# 03_-_28PINS_SCHEMATIC.net
KiCad netlist of a schematic drawn in Altium Designer
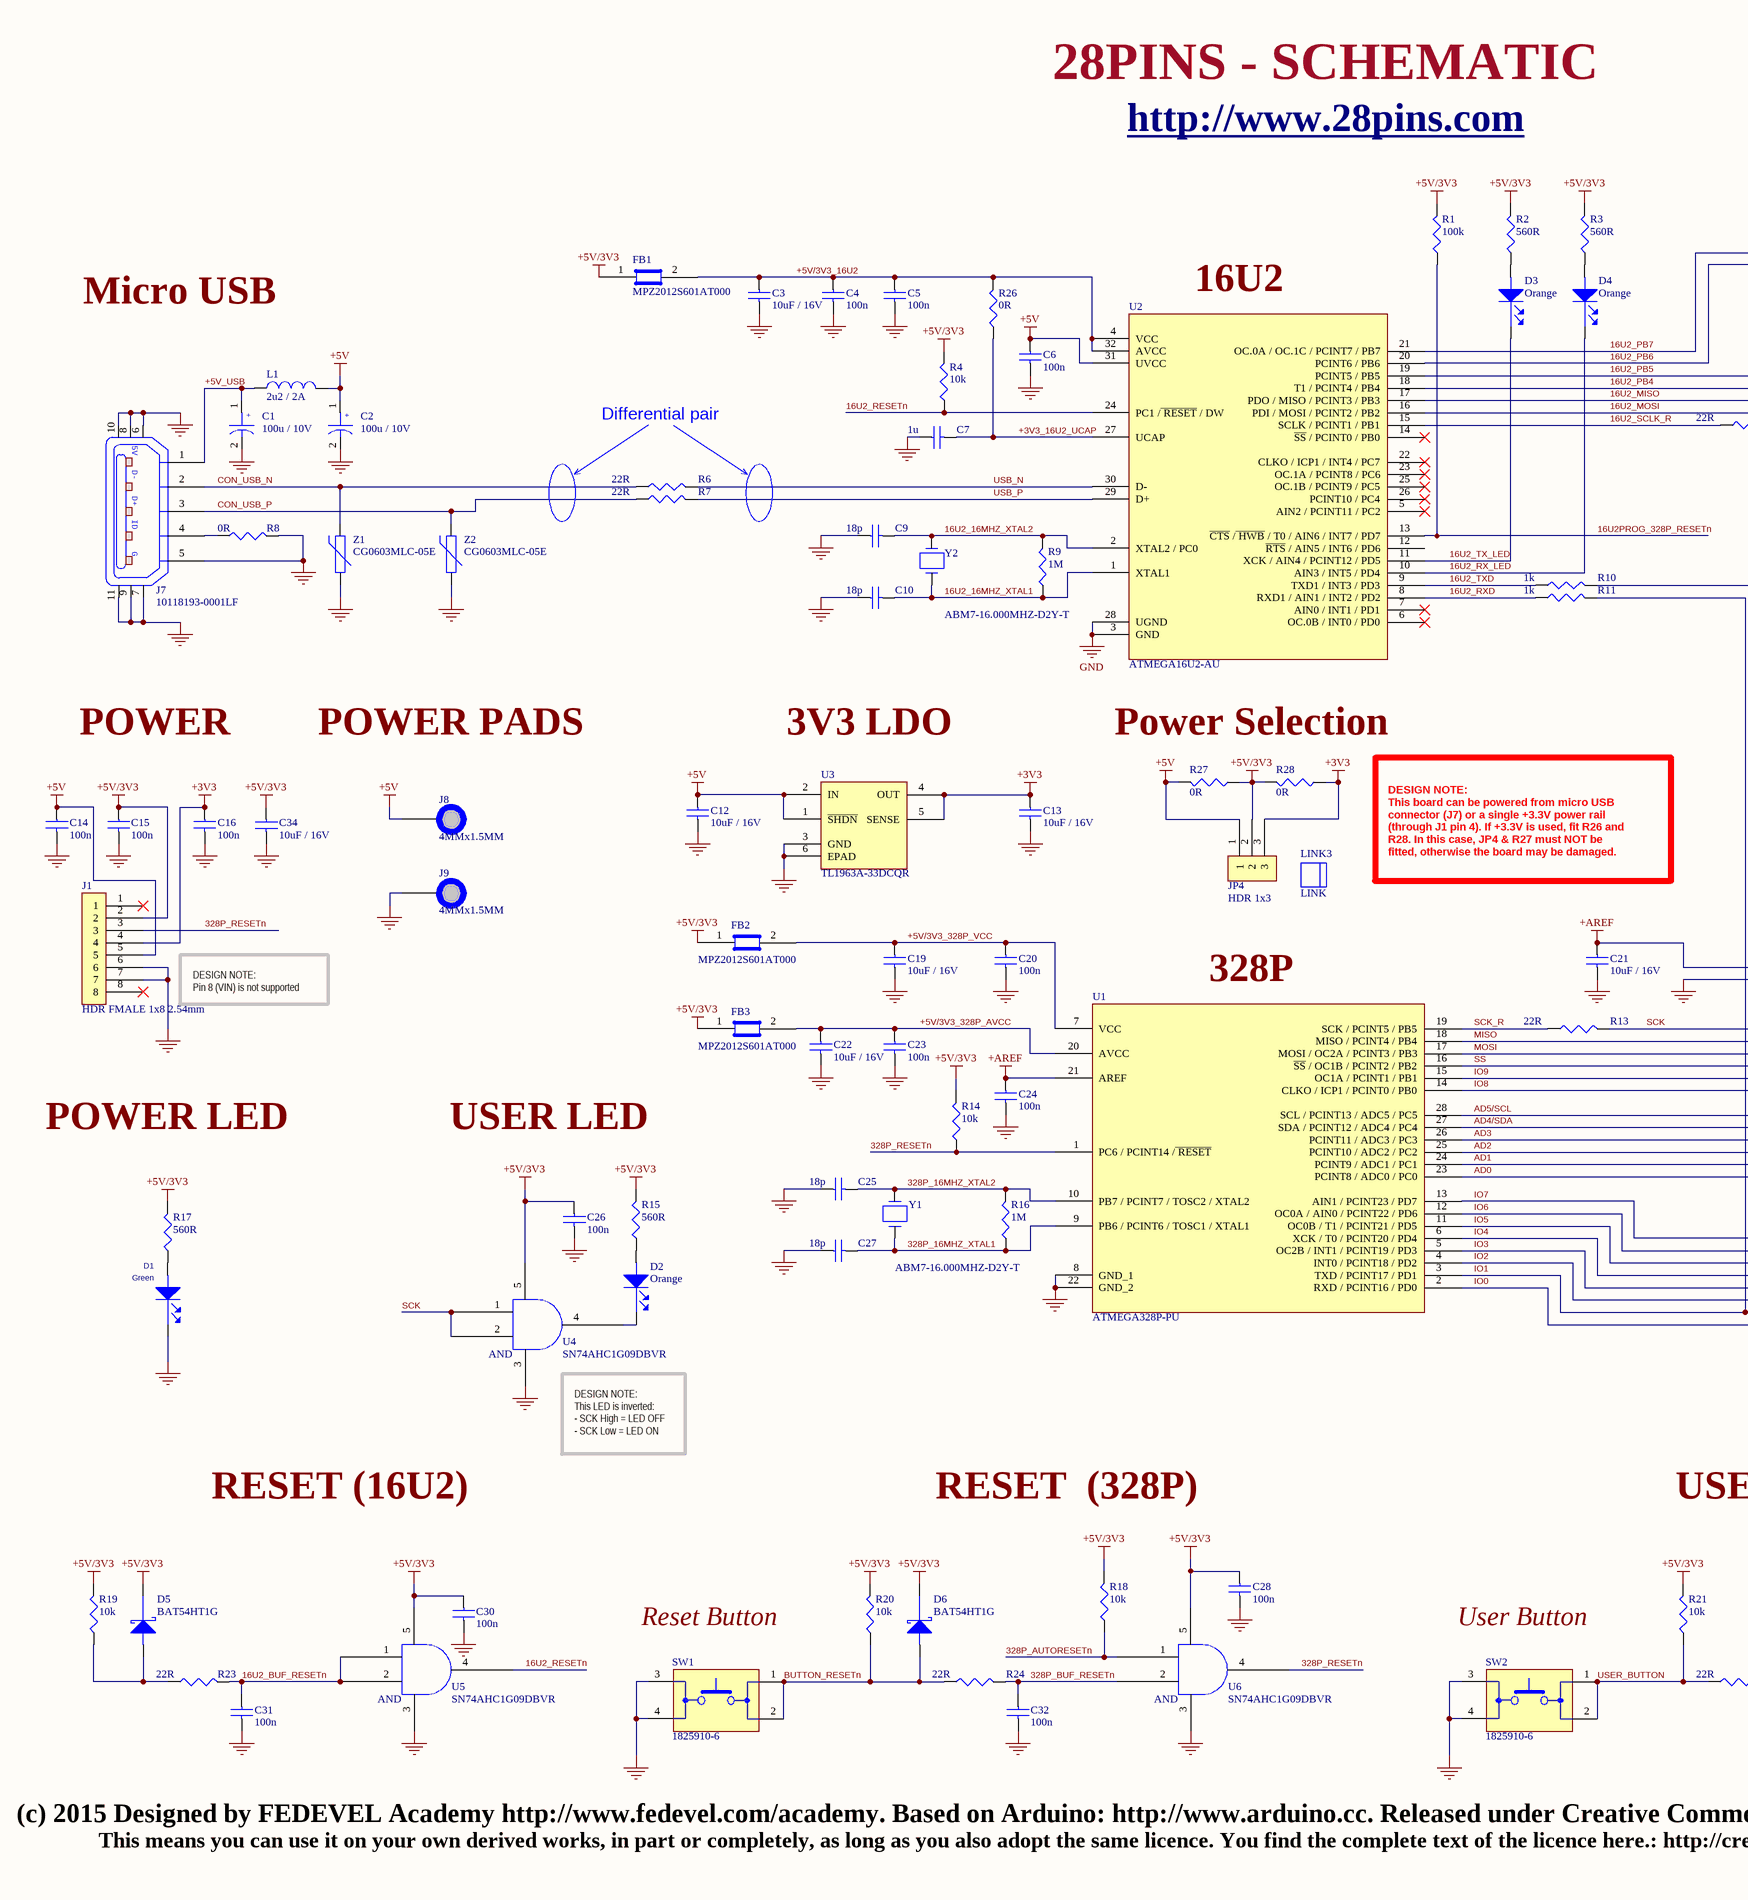
[diagram p0: [03] - 28PINS SCHEMATIC.SchDoc, left]
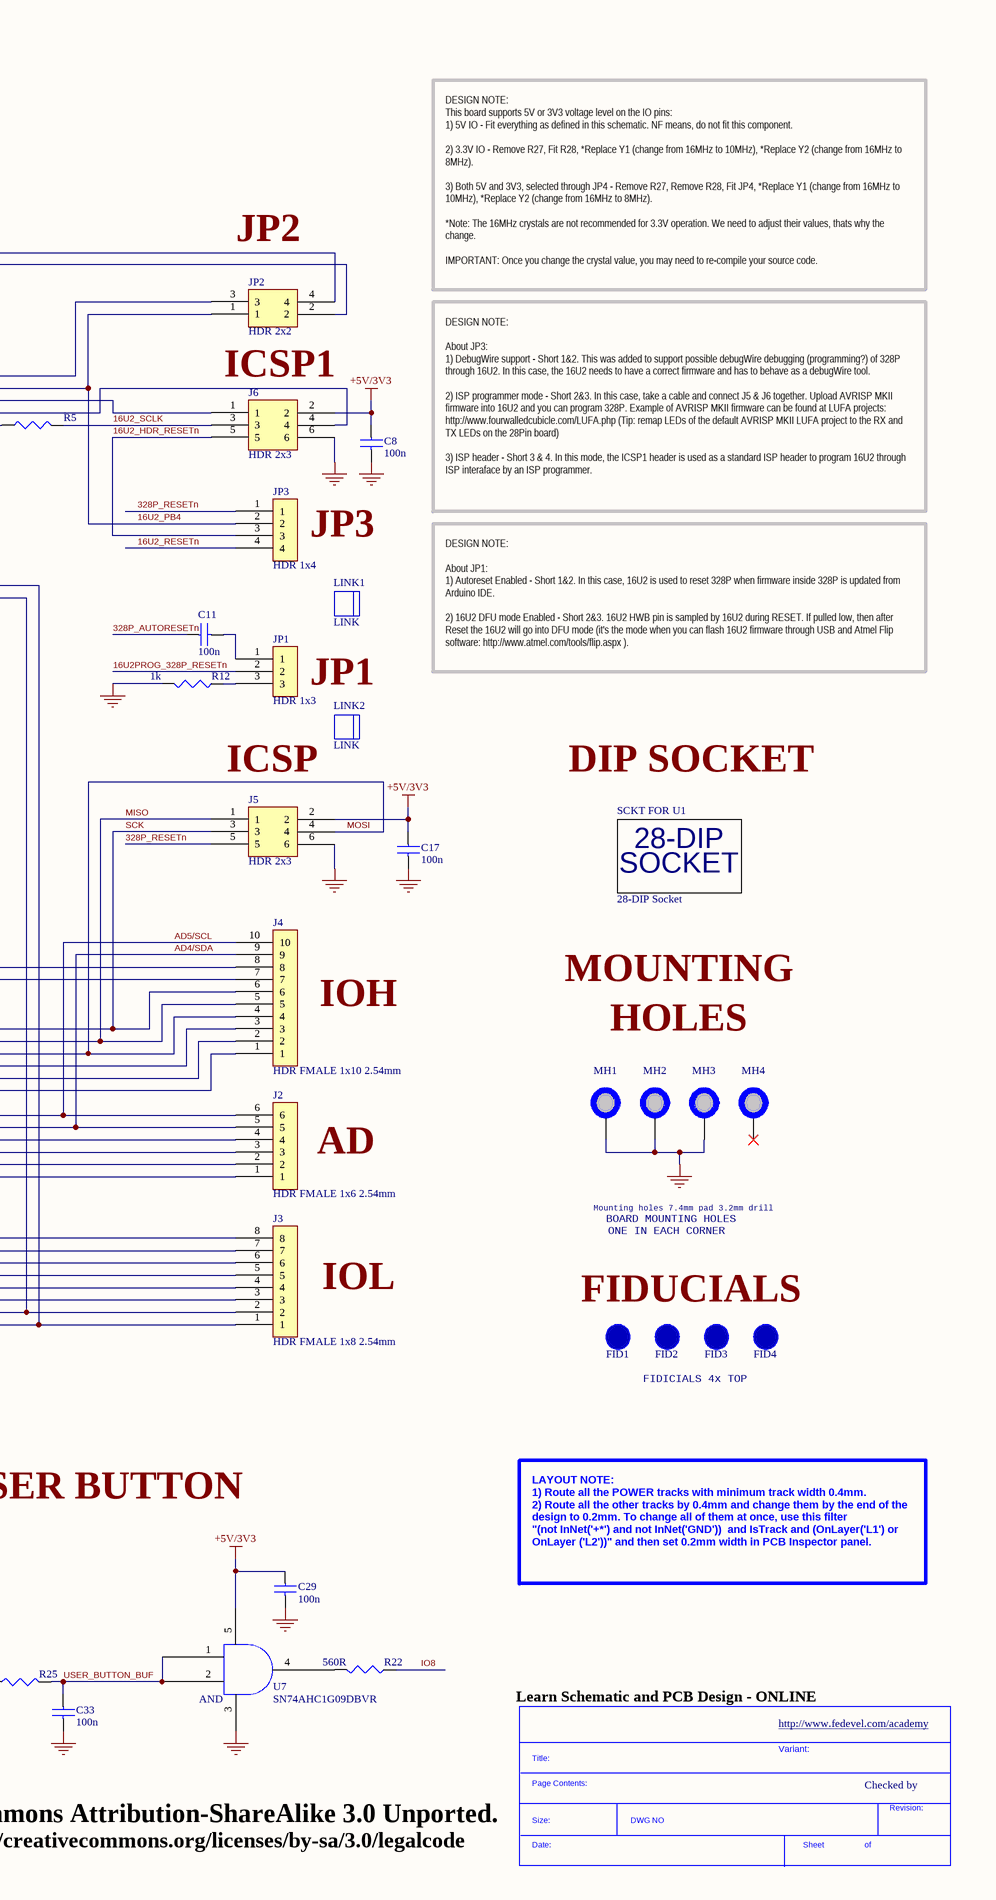
[diagram p1: [03] - 28PINS SCHEMATIC.SchDoc, right]

(export (version "E")
  (design (tool "Eeschema 10.0.6"))
  (components
    (comp (ref "C1")
      (value "100u / 10V")
      (footprint "C_ALU_C_SIZE")
      (description "CAP ALUM 100UF 10V 20% SMD")
      (fields
        (field (name "MANUFACTURER") "Panasonic Electronic Components")
        (field (name "MANUFACTURER PART NUMBER") "EEE-1AA101WR")
        (field (name ".CREATOR") "MM")
        (field (name ".CHECKED PCB") "RF")
        (field (name ".CHECKED SCH") "RF")
      )
      (libsource (lib "Integrated_Library_FEDEVEL_APR_2015") (part "EEE-1AA101WR"))
    )
    (comp (ref "C2")
      (value "100u / 10V")
      (footprint "C_ALU_C_SIZE")
      (description "CAP ALUM 100UF 10V 20% SMD")
      (fields
        (field (name "MANUFACTURER") "Panasonic Electronic Components")
        (field (name "MANUFACTURER PART NUMBER") "EEE-1AA101WR")
        (field (name ".CREATOR") "MM")
        (field (name ".CHECKED PCB") "RF")
        (field (name ".CHECKED SCH") "RF")
      )
      (libsource (lib "Integrated_Library_FEDEVEL_APR_2015") (part "EEE-1AA101WR"))
    )
    (comp (ref "C3")
      (value "10uF / 16V")
      (footprint "C0805")
      (description "CAP CER 10UF 16V 20% X5R 0805")
      (fields
        (field (name "MANUFACTURER") "TDK Corporation")
        (field (name "MANUFACTURER PART NUMBER") "C2012X5R1C106M/1.25")
      )
      (libsource (lib "Integrated_Library_FEDEVEL_APR_2015") (part "C2012X5R1C106M"))
    )
    (comp (ref "C4")
      (value "100n")
      (footprint "C0805")
      (description "CAP CER 0.1UF 50V 10% X7R 0805")
      (fields
        (field (name "MANUFACTURER") "TDK Corporation")
        (field (name "MANUFACTURER PART NUMBER") "C2012X7R1H104K085AA")
        (field (name ".CREATOR") "MM")
        (field (name ".CHECKED PCB") "RF")
        (field (name ".CHECKED SCH") "RF")
      )
      (libsource (lib "Integrated_Library_FEDEVEL_APR_2015") (part "C2012X7R1H104K085AA"))
    )
    (comp (ref "C5")
      (value "100n")
      (footprint "C0805")
      (description "CAP CER 0.1UF 50V 10% X7R 0805")
      (fields
        (field (name "MANUFACTURER") "TDK Corporation")
        (field (name "MANUFACTURER PART NUMBER") "C2012X7R1H104K085AA")
        (field (name ".CREATOR") "MM")
        (field (name ".CHECKED PCB") "RF")
        (field (name ".CHECKED SCH") "RF")
      )
      (libsource (lib "Integrated_Library_FEDEVEL_APR_2015") (part "C2012X7R1H104K085AA"))
    )
    (comp (ref "C6")
      (value "100n")
      (footprint "C0805")
      (description "CAP CER 0.1UF 50V 10% X7R 0805")
      (fields
        (field (name "MANUFACTURER") "TDK Corporation")
        (field (name "MANUFACTURER PART NUMBER") "C2012X7R1H104K085AA")
        (field (name ".CREATOR") "MM")
        (field (name ".CHECKED PCB") "RF")
        (field (name ".CHECKED SCH") "RF")
      )
      (libsource (lib "Integrated_Library_FEDEVEL_APR_2015") (part "C2012X7R1H104K085AA"))
    )
    (comp (ref "C7")
      (value "1u")
      (footprint "C0805")
      (description "CAP CER 1UF 25V 10% X5R 0805")
      (fields
        (field (name "MANUFACTURER") "TDK Corporation")
        (field (name "MANUFACTURER PART NUMBER") "C2012X5R1E105K125AA")
        (field (name ".CREATOR") "MM")
        (field (name ".CHECKED PCB") "RF")
        (field (name ".CHECKED SCH") "RF")
      )
      (libsource (lib "Integrated_Library_FEDEVEL_APR_2015") (part "C2012X5R1E105K125AA"))
    )
    (comp (ref "C8")
      (value "100n")
      (footprint "C0805")
      (description "CAP CER 0.1UF 50V 10% X7R 0805")
      (fields
        (field (name "MANUFACTURER") "TDK Corporation")
        (field (name "MANUFACTURER PART NUMBER") "C2012X7R1H104K085AA")
        (field (name ".CREATOR") "MM")
        (field (name ".CHECKED PCB") "RF")
        (field (name ".CHECKED SCH") "RF")
      )
      (libsource (lib "Integrated_Library_FEDEVEL_APR_2015") (part "C2012X7R1H104K085AA"))
    )
    (comp (ref "C9")
      (value "18p")
      (footprint "C0805")
      (description "CAP CER 18PF 50V 5% NP0 0805")
      (fields
        (field (name "MANUFACTURER") "Kemet")
        (field (name "MANUFACTURER PART NUMBER") "C0805C180J5GACTU")
        (field (name ".CREATOR") "MM")
        (field (name ".CHECKED PCB") "RF")
        (field (name ".CHECKED SCH") "RF")
      )
      (libsource (lib "Integrated_Library_FEDEVEL_APR_2015") (part "C0805C180J5GACTU"))
    )
    (comp (ref "C10")
      (value "18p")
      (footprint "C0805")
      (description "CAP CER 18PF 50V 5% NP0 0805")
      (fields
        (field (name "MANUFACTURER") "Kemet")
        (field (name "MANUFACTURER PART NUMBER") "C0805C180J5GACTU")
        (field (name ".CREATOR") "MM")
        (field (name ".CHECKED PCB") "RF")
        (field (name ".CHECKED SCH") "RF")
      )
      (libsource (lib "Integrated_Library_FEDEVEL_APR_2015") (part "C0805C180J5GACTU"))
    )
    (comp (ref "C11")
      (value "100n")
      (footprint "C0805")
      (description "CAP CER 0.1UF 50V 10% X7R 0805")
      (fields
        (field (name "MANUFACTURER") "TDK Corporation")
        (field (name "MANUFACTURER PART NUMBER") "C2012X7R1H104K085AA")
        (field (name ".CREATOR") "MM")
        (field (name ".CHECKED PCB") "RF")
        (field (name ".CHECKED SCH") "RF")
      )
      (libsource (lib "Integrated_Library_FEDEVEL_APR_2015") (part "C2012X7R1H104K085AA"))
    )
    (comp (ref "C12")
      (value "10uF / 16V")
      (footprint "C0805")
      (description "CAP CER 10UF 16V 20% X5R 0805")
      (fields
        (field (name "MANUFACTURER") "TDK Corporation")
        (field (name "MANUFACTURER PART NUMBER") "C2012X5R1C106M/1.25")
      )
      (libsource (lib "Integrated_Library_FEDEVEL_APR_2015") (part "C2012X5R1C106M"))
    )
    (comp (ref "C13")
      (value "10uF / 16V")
      (footprint "C0805")
      (description "CAP CER 10UF 16V 20% X5R 0805")
      (fields
        (field (name "MANUFACTURER") "TDK Corporation")
        (field (name "MANUFACTURER PART NUMBER") "C2012X5R1C106M/1.25")
      )
      (libsource (lib "Integrated_Library_FEDEVEL_APR_2015") (part "C2012X5R1C106M"))
    )
    (comp (ref "C14")
      (value "100n")
      (footprint "C0805")
      (description "CAP CER 0.1UF 50V 10% X7R 0805")
      (fields
        (field (name "MANUFACTURER") "TDK Corporation")
        (field (name "MANUFACTURER PART NUMBER") "C2012X7R1H104K085AA")
        (field (name ".CREATOR") "MM")
        (field (name ".CHECKED PCB") "RF")
        (field (name ".CHECKED SCH") "RF")
      )
      (libsource (lib "Integrated_Library_FEDEVEL_APR_2015") (part "C2012X7R1H104K085AA"))
    )
    (comp (ref "C15")
      (value "100n")
      (footprint "C0805")
      (description "CAP CER 0.1UF 50V 10% X7R 0805")
      (fields
        (field (name "MANUFACTURER") "TDK Corporation")
        (field (name "MANUFACTURER PART NUMBER") "C2012X7R1H104K085AA")
        (field (name ".CREATOR") "MM")
        (field (name ".CHECKED PCB") "RF")
        (field (name ".CHECKED SCH") "RF")
      )
      (libsource (lib "Integrated_Library_FEDEVEL_APR_2015") (part "C2012X7R1H104K085AA"))
    )
    (comp (ref "C16")
      (value "100n")
      (footprint "C0805")
      (description "CAP CER 0.1UF 50V 10% X7R 0805")
      (fields
        (field (name "MANUFACTURER") "TDK Corporation")
        (field (name "MANUFACTURER PART NUMBER") "C2012X7R1H104K085AA")
        (field (name ".CREATOR") "MM")
        (field (name ".CHECKED PCB") "RF")
        (field (name ".CHECKED SCH") "RF")
      )
      (libsource (lib "Integrated_Library_FEDEVEL_APR_2015") (part "C2012X7R1H104K085AA"))
    )
    (comp (ref "C17")
      (value "100n")
      (footprint "C0805")
      (description "CAP CER 0.1UF 50V 10% X7R 0805")
      (fields
        (field (name "MANUFACTURER") "TDK Corporation")
        (field (name "MANUFACTURER PART NUMBER") "C2012X7R1H104K085AA")
        (field (name ".CREATOR") "MM")
        (field (name ".CHECKED PCB") "RF")
        (field (name ".CHECKED SCH") "RF")
      )
      (libsource (lib "Integrated_Library_FEDEVEL_APR_2015") (part "C2012X7R1H104K085AA"))
    )
    (comp (ref "C19")
      (value "10uF / 16V")
      (footprint "C0805")
      (description "CAP CER 10UF 16V 20% X5R 0805")
      (fields
        (field (name "MANUFACTURER") "TDK Corporation")
        (field (name "MANUFACTURER PART NUMBER") "C2012X5R1C106M/1.25")
      )
      (libsource (lib "Integrated_Library_FEDEVEL_APR_2015") (part "C2012X5R1C106M"))
    )
    (comp (ref "C20")
      (value "100n")
      (footprint "C0805")
      (description "CAP CER 0.1UF 50V 10% X7R 0805")
      (fields
        (field (name "MANUFACTURER") "TDK Corporation")
        (field (name "MANUFACTURER PART NUMBER") "C2012X7R1H104K085AA")
        (field (name ".CREATOR") "MM")
        (field (name ".CHECKED PCB") "RF")
        (field (name ".CHECKED SCH") "RF")
      )
      (libsource (lib "Integrated_Library_FEDEVEL_APR_2015") (part "C2012X7R1H104K085AA"))
    )
    (comp (ref "C21")
      (value "10uF / 16V")
      (footprint "C0805")
      (description "CAP CER 10UF 16V 20% X5R 0805")
      (fields
        (field (name "MANUFACTURER") "TDK Corporation")
        (field (name "MANUFACTURER PART NUMBER") "C2012X5R1C106M/1.25")
      )
      (libsource (lib "Integrated_Library_FEDEVEL_APR_2015") (part "C2012X5R1C106M"))
    )
    (comp (ref "C22")
      (value "10uF / 16V")
      (footprint "C0805")
      (description "CAP CER 10UF 16V 20% X5R 0805")
      (fields
        (field (name "MANUFACTURER") "TDK Corporation")
        (field (name "MANUFACTURER PART NUMBER") "C2012X5R1C106M/1.25")
      )
      (libsource (lib "Integrated_Library_FEDEVEL_APR_2015") (part "C2012X5R1C106M"))
    )
    (comp (ref "C23")
      (value "100n")
      (footprint "C0805")
      (description "CAP CER 0.1UF 50V 10% X7R 0805")
      (fields
        (field (name "MANUFACTURER") "TDK Corporation")
        (field (name "MANUFACTURER PART NUMBER") "C2012X7R1H104K085AA")
        (field (name ".CREATOR") "MM")
        (field (name ".CHECKED PCB") "RF")
        (field (name ".CHECKED SCH") "RF")
      )
      (libsource (lib "Integrated_Library_FEDEVEL_APR_2015") (part "C2012X7R1H104K085AA"))
    )
    (comp (ref "C24")
      (value "100n")
      (footprint "C0805")
      (description "CAP CER 0.1UF 50V 10% X7R 0805")
      (fields
        (field (name "MANUFACTURER") "TDK Corporation")
        (field (name "MANUFACTURER PART NUMBER") "C2012X7R1H104K085AA")
        (field (name ".CREATOR") "MM")
        (field (name ".CHECKED PCB") "RF")
        (field (name ".CHECKED SCH") "RF")
      )
      (libsource (lib "Integrated_Library_FEDEVEL_APR_2015") (part "C2012X7R1H104K085AA"))
    )
    (comp (ref "C25")
      (value "18p")
      (footprint "C0805")
      (description "CAP CER 18PF 50V 5% NP0 0805")
      (fields
        (field (name "MANUFACTURER") "Kemet")
        (field (name "MANUFACTURER PART NUMBER") "C0805C180J5GACTU")
        (field (name ".CREATOR") "MM")
        (field (name ".CHECKED PCB") "RF")
        (field (name ".CHECKED SCH") "RF")
      )
      (libsource (lib "Integrated_Library_FEDEVEL_APR_2015") (part "C0805C180J5GACTU"))
    )
    (comp (ref "C26")
      (value "100n")
      (footprint "C0805")
      (description "CAP CER 0.1UF 50V 10% X7R 0805")
      (fields
        (field (name "MANUFACTURER") "TDK Corporation")
        (field (name "MANUFACTURER PART NUMBER") "C2012X7R1H104K085AA")
        (field (name ".CREATOR") "MM")
        (field (name ".CHECKED PCB") "RF")
        (field (name ".CHECKED SCH") "RF")
      )
      (libsource (lib "Integrated_Library_FEDEVEL_APR_2015") (part "C2012X7R1H104K085AA"))
    )
    (comp (ref "C27")
      (value "18p")
      (footprint "C0805")
      (description "CAP CER 18PF 50V 5% NP0 0805")
      (fields
        (field (name "MANUFACTURER") "Kemet")
        (field (name "MANUFACTURER PART NUMBER") "C0805C180J5GACTU")
        (field (name ".CREATOR") "MM")
        (field (name ".CHECKED PCB") "RF")
        (field (name ".CHECKED SCH") "RF")
      )
      (libsource (lib "Integrated_Library_FEDEVEL_APR_2015") (part "C0805C180J5GACTU"))
    )
    (comp (ref "C28")
      (value "100n")
      (footprint "C0805")
      (description "CAP CER 0.1UF 50V 10% X7R 0805")
      (fields
        (field (name "MANUFACTURER") "TDK Corporation")
        (field (name "MANUFACTURER PART NUMBER") "C2012X7R1H104K085AA")
        (field (name ".CREATOR") "MM")
        (field (name ".CHECKED PCB") "RF")
        (field (name ".CHECKED SCH") "RF")
      )
      (libsource (lib "Integrated_Library_FEDEVEL_APR_2015") (part "C2012X7R1H104K085AA"))
    )
    (comp (ref "C29")
      (value "100n")
      (footprint "C0805")
      (description "CAP CER 0.1UF 50V 10% X7R 0805")
      (fields
        (field (name "MANUFACTURER") "TDK Corporation")
        (field (name "MANUFACTURER PART NUMBER") "C2012X7R1H104K085AA")
        (field (name ".CREATOR") "MM")
        (field (name ".CHECKED PCB") "RF")
        (field (name ".CHECKED SCH") "RF")
      )
      (libsource (lib "Integrated_Library_FEDEVEL_APR_2015") (part "C2012X7R1H104K085AA"))
    )
    (comp (ref "C30")
      (value "100n")
      (footprint "C0805")
      (description "CAP CER 0.1UF 50V 10% X7R 0805")
      (fields
        (field (name "MANUFACTURER") "TDK Corporation")
        (field (name "MANUFACTURER PART NUMBER") "C2012X7R1H104K085AA")
        (field (name ".CREATOR") "MM")
        (field (name ".CHECKED PCB") "RF")
        (field (name ".CHECKED SCH") "RF")
      )
      (libsource (lib "Integrated_Library_FEDEVEL_APR_2015") (part "C2012X7R1H104K085AA"))
    )
    (comp (ref "C31")
      (value "100n")
      (footprint "C0805")
      (description "CAP CER 0.1UF 50V 10% X7R 0805")
      (fields
        (field (name "MANUFACTURER") "TDK Corporation")
        (field (name "MANUFACTURER PART NUMBER") "C2012X7R1H104K085AA")
        (field (name ".CREATOR") "MM")
        (field (name ".CHECKED PCB") "RF")
        (field (name ".CHECKED SCH") "RF")
      )
      (libsource (lib "Integrated_Library_FEDEVEL_APR_2015") (part "C2012X7R1H104K085AA"))
    )
    (comp (ref "C32")
      (value "100n")
      (footprint "C0805")
      (description "CAP CER 0.1UF 50V 10% X7R 0805")
      (fields
        (field (name "MANUFACTURER") "TDK Corporation")
        (field (name "MANUFACTURER PART NUMBER") "C2012X7R1H104K085AA")
        (field (name ".CREATOR") "MM")
        (field (name ".CHECKED PCB") "RF")
        (field (name ".CHECKED SCH") "RF")
      )
      (libsource (lib "Integrated_Library_FEDEVEL_APR_2015") (part "C2012X7R1H104K085AA"))
    )
    (comp (ref "C33")
      (value "100n")
      (footprint "C0805")
      (description "CAP CER 0.1UF 50V 10% X7R 0805")
      (fields
        (field (name "MANUFACTURER") "TDK Corporation")
        (field (name "MANUFACTURER PART NUMBER") "C2012X7R1H104K085AA")
        (field (name ".CREATOR") "MM")
        (field (name ".CHECKED PCB") "RF")
        (field (name ".CHECKED SCH") "RF")
      )
      (libsource (lib "Integrated_Library_FEDEVEL_APR_2015") (part "C2012X7R1H104K085AA"))
    )
    (comp (ref "C34")
      (value "10uF / 16V")
      (footprint "C0805")
      (description "CAP CER 10UF 16V 20% X5R 0805")
      (fields
        (field (name "MANUFACTURER") "TDK Corporation")
        (field (name "MANUFACTURER PART NUMBER") "C2012X5R1C106M/1.25")
      )
      (libsource (lib "Integrated_Library_FEDEVEL_APR_2015") (part "C2012X5R1C106M"))
    )
    (comp (ref "D1")
      (value "Green")
      (footprint "LED_0603")
      (description "LED SMARTLED GREEN 570NM 0603")
      (fields
        (field (name "MANUFACTURER") "OSRAM Opto Semiconductors Inc")
        (field (name "MANUFACTURER PART NUMBER") "LG L29K-G2J1-24-Z")
      )
      (libsource (lib "Integrated_Library_FEDEVEL_APR_2015") (part "LG L29K-G2J1-24-Z"))
    )
    (comp (ref "D2")
      (value "Orange")
      (footprint "LED_0603")
      (description "LED SMARTLED ORANGE 606NM 0603")
      (fields
        (field (name "MANUFACTURER") "OSRAM Opto Semiconductors Inc")
        (field (name "MANUFACTURER PART NUMBER") "LO L29K-H2K1-24-Z")
      )
      (libsource (lib "Integrated_Library_FEDEVEL_APR_2015") (part "LO L29K-H2K1-24-Z"))
    )
    (comp (ref "D3")
      (value "Orange")
      (footprint "LED_0603")
      (description "LED SMARTLED ORANGE 606NM 0603")
      (fields
        (field (name "MANUFACTURER") "OSRAM Opto Semiconductors Inc")
        (field (name "MANUFACTURER PART NUMBER") "LO L29K-H2K1-24-Z")
      )
      (libsource (lib "Integrated_Library_FEDEVEL_APR_2015") (part "LO L29K-H2K1-24-Z"))
    )
    (comp (ref "D4")
      (value "Orange")
      (footprint "LED_0603")
      (description "LED SMARTLED ORANGE 606NM 0603")
      (fields
        (field (name "MANUFACTURER") "OSRAM Opto Semiconductors Inc")
        (field (name "MANUFACTURER PART NUMBER") "LO L29K-H2K1-24-Z")
      )
      (libsource (lib "Integrated_Library_FEDEVEL_APR_2015") (part "LO L29K-H2K1-24-Z"))
    )
    (comp (ref "D5")
      (value "BAT54HT1G")
      (footprint "SOD323")
      (description "DIODE SCHOTTKY 30V 0.2A SOD323")
      (fields (field (name "MANUFACTURER") "Fairchild Semiconductor") (field (name ".CREATOR") "MM"))
      (libsource (lib "Integrated_Library_FEDEVEL_APR_2015") (part "BAT54HT1G"))
    )
    (comp (ref "D6")
      (value "BAT54HT1G")
      (footprint "SOD323")
      (description "DIODE SCHOTTKY 30V 0.2A SOD323")
      (fields (field (name "MANUFACTURER") "Fairchild Semiconductor") (field (name ".CREATOR") "MM"))
      (libsource (lib "Integrated_Library_FEDEVEL_APR_2015") (part "BAT54HT1G"))
    )
    (comp (ref "FB1")
      (value "MPZ2012S601AT000")
      (footprint "C0805")
      (description "FERRITE CHIP BEAD 600 OHM SMD")
      (fields
        (field (name "MANUFACTURER") "TDK Corporation")
        (field (name ".CREATOR") "MM")
        (field (name ".CHECKED PCB") "RF")
        (field (name ".CHECKED SCH") "RF")
      )
      (libsource (lib "Integrated_Library_FEDEVEL_APR_2015") (part "MPZ2012S601AT000"))
    )
    (comp (ref "FB2")
      (value "MPZ2012S601AT000")
      (footprint "C0805")
      (description "FERRITE CHIP BEAD 600 OHM SMD")
      (fields
        (field (name "MANUFACTURER") "TDK Corporation")
        (field (name ".CREATOR") "MM")
        (field (name ".CHECKED PCB") "RF")
        (field (name ".CHECKED SCH") "RF")
      )
      (libsource (lib "Integrated_Library_FEDEVEL_APR_2015") (part "MPZ2012S601AT000"))
    )
    (comp (ref "FB3")
      (value "MPZ2012S601AT000")
      (footprint "C0805")
      (description "FERRITE CHIP BEAD 600 OHM SMD")
      (fields
        (field (name "MANUFACTURER") "TDK Corporation")
        (field (name ".CREATOR") "MM")
        (field (name ".CHECKED PCB") "RF")
        (field (name ".CHECKED SCH") "RF")
      )
      (libsource (lib "Integrated_Library_FEDEVEL_APR_2015") (part "MPZ2012S601AT000"))
    )
    (comp (ref "FID1")
      (value "FID_1MMC")
      (footprint "FID_40X120D")
      (description "Fiducial 40mil Diameter, 120mil Mask")
      (libsource (lib "Integrated_Library_FEDEVEL_APR_2015") (part "FID_1MMC"))
    )
    (comp (ref "FID2")
      (value "FID_1MMC")
      (footprint "FID_40X120D")
      (description "Fiducial 40mil Diameter, 120mil Mask")
      (libsource (lib "Integrated_Library_FEDEVEL_APR_2015") (part "FID_1MMC"))
    )
    (comp (ref "FID3")
      (value "FID_1MMC")
      (footprint "FID_40X120D")
      (description "Fiducial 40mil Diameter, 120mil Mask")
      (libsource (lib "Integrated_Library_FEDEVEL_APR_2015") (part "FID_1MMC"))
    )
    (comp (ref "FID4")
      (value "FID_1MMC")
      (footprint "FID_40X120D")
      (description "Fiducial 40mil Diameter, 120mil Mask")
      (libsource (lib "Integrated_Library_FEDEVEL_APR_2015") (part "FID_1MMC"))
    )
    (comp (ref "J1")
      (value "HDR FMALE 1x8 2.54mm")
      (footprint "Hdr_Female_1x8_2.54mm")
      (description "08-WAY SIL VERT SOCKET L/FREE")
      (fields
        (field (name "MANUFACTURER") "Harwin Inc")
        (field (name "MANUFACTURER PART NUMBER") "M20-7820842")
        (field (name ".CREATOR") "MM")
        (field (name ".CHECKED PCB") "RF")
        (field (name ".CHECKED SCH") "RF")
      )
      (libsource (lib "Integrated_Library_FEDEVEL_APR_2015") (part "M20-7820842"))
    )
    (comp (ref "J2")
      (value "HDR FMALE 1x6 2.54mm")
      (footprint "Hdr_Female_1x6_2.54mm")
      (description "06-WAY SIL VERT SOCKET L/FREE")
      (fields
        (field (name "MANUFACTURER") "Harwin Inc")
        (field (name "MANUFACTURER PART NUMBER") "M20-7820646")
        (field (name ".CHECKED PCB") "MM")
        (field (name ".CHECKED SCH") "MM")
        (field (name ".CREATOR") "MM")
      )
      (libsource (lib "Integrated_Library_FEDEVEL_APR_2015") (part "M20-7820646"))
    )
    (comp (ref "J3")
      (value "HDR FMALE 1x8 2.54mm")
      (footprint "Hdr_Female_1x8_2.54mm")
      (description "08-WAY SIL VERT SOCKET L/FREE")
      (fields
        (field (name "MANUFACTURER") "Harwin Inc")
        (field (name "MANUFACTURER PART NUMBER") "M20-7820842")
        (field (name ".CREATOR") "MM")
        (field (name ".CHECKED PCB") "RF")
        (field (name ".CHECKED SCH") "RF")
      )
      (libsource (lib "") (part "M20-7820842_1"))
    )
    (comp (ref "J4")
      (value "HDR FMALE 1x10 2.54mm")
      (footprint "Hdr_Female_1x10_2.54mm")
      (description "10-WAY SIL VERT SOCKET L/FREE")
      (fields
        (field (name "MANUFACTURER") "Harwin Inc")
        (field (name "MANUFACTURER PART NUMBER") "M20-7821046")
        (field (name ".CREATOR") "MM")
        (field (name ".CHECKED PCB") "RF")
        (field (name ".CHECKED SCH") "RF")
      )
      (libsource (lib "Integrated_Library_FEDEVEL_APR_2015") (part "M20-7821046"))
    )
    (comp (ref "J5")
      (value "HDR 2x3")
      (footprint "HDR_2x3_2.54MM")
      (description "CONN HEADER 6POS .100 STR 30AU")
      (fields
        (field (name "MANUFACTURER") "FCI")
        (field (name "MANUFACTURER PART NUMBER") "67997-106HLF")
        (field (name ".CREATOR") "MM")
        (field (name ".CHECKED PCB") "RF")
        (field (name ".CHECKED SCH") "RF")
      )
      (libsource (lib "Integrated_Library_FEDEVEL_APR_2015") (part "67997-106HLF"))
    )
    (comp (ref "J6")
      (value "HDR 2x3")
      (footprint "HDR_2x3_2.54MM")
      (description "CONN HEADER 6POS .100 STR 30AU")
      (fields
        (field (name "MANUFACTURER") "FCI")
        (field (name "MANUFACTURER PART NUMBER") "67997-106HLF")
        (field (name ".CREATOR") "MM")
        (field (name ".CHECKED PCB") "RF")
        (field (name ".CHECKED SCH") "RF")
      )
      (libsource (lib "Integrated_Library_FEDEVEL_APR_2015") (part "67997-106HLF"))
    )
    (comp (ref "J7")
      (value "10118193-0001LF")
      (footprint "10118193")
      (description "CONN USB MICRO B RECPT SMT R/A")
      (fields
        (field (name "MANUFACTURER") "FCI")
        (field (name ".CREATOR") "MM")
        (field (name ".CHECKED PCB") "RF")
        (field (name ".CHECKED SCH") "MM")
      )
      (libsource (lib "Integrated_Library_FEDEVEL_APR_2015") (part "10118193-0001LF"))
    )
    (comp (ref "J8")
      (value "4MMx1.5MM")
      (footprint "PAD_WITH_HOLE_4MMx1.5MM")
      (description "Pad with a hole 4mm x 1.5mm")
      (libsource (lib "Integrated_Library_FEDEVEL_APR_2015") (part "PAD_WITH_HOLE_4MMx1.5MM"))
    )
    (comp (ref "J9")
      (value "4MMx1.5MM")
      (footprint "PAD_WITH_HOLE_4MMx1.5MM")
      (description "Pad with a hole 4mm x 1.5mm")
      (libsource (lib "Integrated_Library_FEDEVEL_APR_2015") (part "PAD_WITH_HOLE_4MMx1.5MM"))
    )
    (comp (ref "JP1")
      (value "HDR 1x3")
      (footprint "Hdr_1x3_2.54mm")
      (description "BERGSTIK II .100\" SR STRAIGHT")
      (fields
        (field (name "MANUFACTURER") "FCI")
        (field (name "MANUFACTURER PART NUMBER") "68000-103HLF")
        (field (name ".CREATOR") "MM")
      )
      (libsource (lib "") (part "68000-103HLF_1"))
    )
    (comp (ref "JP2")
      (value "HDR 2x2")
      (footprint "HDR_2x2_2.54MM")
      (description "CONN HEADER 4POS .100 STR 15AU")
      (fields
        (field (name "MANUFACTURER") "FCI")
        (field (name "MANUFACTURER PART NUMBER") "68602-204HLF")
        (field (name ".CREATOR") "MM")
        (field (name ".CHECKED PCB") "RF")
        (field (name ".CHECKED SCH") "RF")
      )
      (libsource (lib "Integrated_Library_FEDEVEL_APR_2015") (part "68602-204HLF"))
    )
    (comp (ref "JP3")
      (value "HDR 1x4")
      (footprint "HDR_1x4_2.54MM")
      (description "CONN HEADER 4POS .100 STR 15AU")
      (fields
        (field (name "MANUFACTURER") "FCI")
        (field (name "MANUFACTURER PART NUMBER") "68001-204HLF")
        (field (name ".CHECKED PCB") "RF")
        (field (name ".CHECKED SCH") "RF")
      )
      (libsource (lib "Integrated_Library_FEDEVEL_APR_2015") (part "68001-204HLF"))
    )
    (comp (ref "JP4")
      (value "HDR 1x3")
      (footprint "Hdr_1x3_2.54mm")
      (description "BERGSTIK II .100\" SR STRAIGHT")
      (fields
        (field (name "MANUFACTURER") "FCI")
        (field (name "MANUFACTURER PART NUMBER") "68000-103HLF")
        (field (name ".CREATOR") "MM")
      )
      (libsource (lib "Integrated_Library_FEDEVEL_APR_2015") (part "68000-103HLF"))
    )
    (comp (ref "L1")
      (value "2u2 / 2A")
      (footprint "C1210_IND")
      (description "FIXED IND 2.2UH 2A 80 MOHM SMD")
      (fields
        (field (name "MANUFACTURER") "Kemet")
        (field (name "MANUFACTURER PART NUMBER") "L1210R2R2MDWIT")
        (field (name ".CREATOR") "MM")
        (field (name ".CHECKED PCB") "RF")
        (field (name ".CHECKED SCH") "RF")
      )
      (libsource (lib "Integrated_Library_FEDEVEL_APR_2015") (part "L1210R2R2MDWIT"))
    )
    (comp (ref "LINK1")
      (value "LINK")
      (description "CONN JUMPER SHORTING .100\" GOLD")
      (fields
        (field (name "MANUFACTURER") "Sullins Connector Solutions")
        (field (name "MANUFACTURER PART NUMBER") "QPC02SXGN-RC")
      )
      (libsource (lib "Integrated_Library_FEDEVEL_APR_2015") (part "QPC02SXGN-RC"))
    )
    (comp (ref "LINK2")
      (value "LINK")
      (description "CONN JUMPER SHORTING .100\" GOLD")
      (fields
        (field (name "MANUFACTURER") "Sullins Connector Solutions")
        (field (name "MANUFACTURER PART NUMBER") "QPC02SXGN-RC")
      )
      (libsource (lib "Integrated_Library_FEDEVEL_APR_2015") (part "QPC02SXGN-RC"))
    )
    (comp (ref "LINK3")
      (value "LINK")
      (description "CONN JUMPER SHORTING .100\" GOLD")
      (fields
        (field (name "MANUFACTURER") "Sullins Connector Solutions")
        (field (name "MANUFACTURER PART NUMBER") "QPC02SXGN-RC")
      )
      (libsource (lib "Integrated_Library_FEDEVEL_APR_2015") (part "QPC02SXGN-RC"))
    )
    (comp (ref "MH1")
      (value "MH_7.4MMC_3.2MMD")
      (footprint "MH_7.4MMD_3.2MMD")
      (description "Mounting Hole 7.4mm Diameter, 3.2mm Drill")
      (fields (field (name ".CREATOR") "MM"))
      (libsource (lib "Integrated_Library_FEDEVEL_APR_2015") (part "MH_7.4MMC_3.2MMD"))
    )
    (comp (ref "MH2")
      (value "MH_7.4MMC_3.2MMD")
      (footprint "MH_7.4MMD_3.2MMD")
      (description "Mounting Hole 7.4mm Diameter, 3.2mm Drill")
      (fields (field (name ".CREATOR") "MM"))
      (libsource (lib "Integrated_Library_FEDEVEL_APR_2015") (part "MH_7.4MMC_3.2MMD"))
    )
    (comp (ref "MH3")
      (value "MH_7.4MMC_3.2MMD")
      (footprint "MH_7.4MMD_3.2MMD")
      (description "Mounting Hole 7.4mm Diameter, 3.2mm Drill")
      (fields (field (name ".CREATOR") "MM"))
      (libsource (lib "Integrated_Library_FEDEVEL_APR_2015") (part "MH_7.4MMC_3.2MMD"))
    )
    (comp (ref "MH4")
      (value "MH_7.4MMNC_3.2MMD")
      (footprint "MH_7.4MMD_3.2MMD_NON_COPPER_NPTH")
      (description "Mounting Hole 7.4mm Diameter (Non Copper), 3.2mm Drill NPTH")
      (libsource (lib "Integrated_Library_FEDEVEL_APR_2015") (part "MH_7.4MMNC_3.2MMD"))
    )
    (comp (ref "R1")
      (value "100k")
      (footprint "R0805")
      (description "RES SMD 100K OHM 1% 1/8W 0805")
      (fields
        (field (name "MANUFACTURER") "Yageo")
        (field (name "MANUFACTURER PART NUMBER") "RC0805FR-07100KL")
        (field (name ".CREATOR") "MM")
        (field (name ".CHECKED PCB") "RF")
        (field (name ".CHECKED SCH") "RF")
      )
      (libsource (lib "Integrated_Library_FEDEVEL_APR_2015") (part "RC0805FR-07100KL"))
    )
    (comp (ref "R2")
      (value "560R")
      (footprint "R0805")
      (description "RES SMD 560 OHM 1% 1/8W 0805")
      (fields
        (field (name "MANUFACTURER") "Yageo")
        (field (name "MANUFACTURER PART NUMBER") "RC0805FR-07560RL")
        (field (name ".CREATOR") "MM")
        (field (name ".CHECKED PCB") "RF")
        (field (name ".CHECKED SCH") "RF")
      )
      (libsource (lib "Integrated_Library_FEDEVEL_APR_2015") (part "RC0805FR-07560RL"))
    )
    (comp (ref "R3")
      (value "560R")
      (footprint "R0805")
      (description "RES SMD 560 OHM 1% 1/8W 0805")
      (fields
        (field (name "MANUFACTURER") "Yageo")
        (field (name "MANUFACTURER PART NUMBER") "RC0805FR-07560RL")
        (field (name ".CREATOR") "MM")
        (field (name ".CHECKED PCB") "RF")
        (field (name ".CHECKED SCH") "RF")
      )
      (libsource (lib "Integrated_Library_FEDEVEL_APR_2015") (part "RC0805FR-07560RL"))
    )
    (comp (ref "R4")
      (value "10k")
      (footprint "R0805")
      (description "RES SMD 10K OHM 1% 1/8W 0805")
      (fields
        (field (name "MANUFACTURER") "Yageo")
        (field (name "MANUFACTURER PART NUMBER") "RC0805FR-0710KL")
        (field (name ".CREATOR") "MM")
        (field (name ".CHECKED PCB") "RF")
        (field (name ".CHECKED SCH") "RF")
      )
      (libsource (lib "Integrated_Library_FEDEVEL_APR_2015") (part "RC0805FR-0710KL"))
    )
    (comp (ref "R5")
      (value "22R")
      (footprint "R0805")
      (description "RES SMD 22 OHM 1% 1/8W 0805")
      (fields
        (field (name "MANUFACTURER") "Yageo")
        (field (name "MANUFACTURER PART NUMBER") "RC0805FR-0722RL")
        (field (name ".CREATOR") "MM")
        (field (name ".CHECKED PCB") "RF")
        (field (name ".CHECKED SCH") "RF")
      )
      (libsource (lib "Integrated_Library_FEDEVEL_APR_2015") (part "RC0805FR-0722RL"))
    )
    (comp (ref "R6")
      (value "22R")
      (footprint "R0805")
      (description "RES SMD 22 OHM 1% 1/8W 0805")
      (fields
        (field (name "MANUFACTURER") "Yageo")
        (field (name "MANUFACTURER PART NUMBER") "RC0805FR-0722RL")
        (field (name ".CREATOR") "MM")
        (field (name ".CHECKED PCB") "RF")
        (field (name ".CHECKED SCH") "RF")
      )
      (libsource (lib "Integrated_Library_FEDEVEL_APR_2015") (part "RC0805FR-0722RL"))
    )
    (comp (ref "R7")
      (value "22R")
      (footprint "R0805")
      (description "RES SMD 22 OHM 1% 1/8W 0805")
      (fields
        (field (name "MANUFACTURER") "Yageo")
        (field (name "MANUFACTURER PART NUMBER") "RC0805FR-0722RL")
        (field (name ".CREATOR") "MM")
        (field (name ".CHECKED PCB") "RF")
        (field (name ".CHECKED SCH") "RF")
      )
      (libsource (lib "Integrated_Library_FEDEVEL_APR_2015") (part "RC0805FR-0722RL"))
    )
    (comp (ref "R8")
      (value "0R")
      (footprint "R0805")
      (description "RES 0.0 OHM 1/8W 0805 SMD")
      (fields
        (field (name "MANUFACTURER") "Yageo")
        (field (name "MANUFACTURER PART NUMBER") "RC0805JR-070RL")
        (field (name ".CHECKED PCB") "RF")
        (field (name ".CHECKED SCH") "RF")
      )
      (libsource (lib "Integrated_Library_FEDEVEL_APR_2015") (part "RC0805JR-070RL"))
    )
    (comp (ref "R9")
      (value "1M")
      (footprint "R0805")
      (description "RES SMD 1M OHM 1% 1/8W 0805")
      (fields
        (field (name "MANUFACTURER") "Yageo")
        (field (name "MANUFACTURER PART NUMBER") "RC0805FR-071ML")
        (field (name ".CREATOR") "MM")
        (field (name ".CHECKED PCB") "RF")
        (field (name ".CHECKED SCH") "RF")
      )
      (libsource (lib "Integrated_Library_FEDEVEL_APR_2015") (part "RC0805FR-071ML"))
    )
    (comp (ref "R10")
      (value "1k")
      (footprint "R0805")
      (description "RES SMD 1K OHM 1% 1/8W 0805")
      (fields
        (field (name "MANUFACTURER") "Yageo")
        (field (name "MANUFACTURER PART NUMBER") "RC0805FR-071KL")
        (field (name ".CREATOR") "MM")
        (field (name ".CHECKED PCB") "RF")
        (field (name ".CHECKED SCH") "RF")
      )
      (libsource (lib "Integrated_Library_FEDEVEL_APR_2015") (part "RC0805FR-071KL"))
    )
    (comp (ref "R11")
      (value "1k")
      (footprint "R0805")
      (description "RES SMD 1K OHM 1% 1/8W 0805")
      (fields
        (field (name "MANUFACTURER") "Yageo")
        (field (name "MANUFACTURER PART NUMBER") "RC0805FR-071KL")
        (field (name ".CREATOR") "MM")
        (field (name ".CHECKED PCB") "RF")
        (field (name ".CHECKED SCH") "RF")
      )
      (libsource (lib "Integrated_Library_FEDEVEL_APR_2015") (part "RC0805FR-071KL"))
    )
    (comp (ref "R12")
      (value "1k")
      (footprint "R0805")
      (description "RES SMD 1K OHM 1% 1/8W 0805")
      (fields
        (field (name "MANUFACTURER") "Yageo")
        (field (name "MANUFACTURER PART NUMBER") "RC0805FR-071KL")
        (field (name ".CREATOR") "MM")
        (field (name ".CHECKED PCB") "RF")
        (field (name ".CHECKED SCH") "RF")
      )
      (libsource (lib "Integrated_Library_FEDEVEL_APR_2015") (part "RC0805FR-071KL"))
    )
    (comp (ref "R13")
      (value "22R")
      (footprint "R0805")
      (description "RES SMD 22 OHM 1% 1/8W 0805")
      (fields
        (field (name "MANUFACTURER") "Yageo")
        (field (name "MANUFACTURER PART NUMBER") "RC0805FR-0722RL")
        (field (name ".CREATOR") "MM")
        (field (name ".CHECKED PCB") "RF")
        (field (name ".CHECKED SCH") "RF")
      )
      (libsource (lib "Integrated_Library_FEDEVEL_APR_2015") (part "RC0805FR-0722RL"))
    )
    (comp (ref "R14")
      (value "10k")
      (footprint "R0805")
      (description "RES SMD 10K OHM 1% 1/8W 0805")
      (fields
        (field (name "MANUFACTURER") "Yageo")
        (field (name "MANUFACTURER PART NUMBER") "RC0805FR-0710KL")
        (field (name ".CREATOR") "MM")
        (field (name ".CHECKED PCB") "RF")
        (field (name ".CHECKED SCH") "RF")
      )
      (libsource (lib "Integrated_Library_FEDEVEL_APR_2015") (part "RC0805FR-0710KL"))
    )
    (comp (ref "R15")
      (value "560R")
      (footprint "R0805")
      (description "RES SMD 560 OHM 1% 1/8W 0805")
      (fields
        (field (name "MANUFACTURER") "Yageo")
        (field (name "MANUFACTURER PART NUMBER") "RC0805FR-07560RL")
        (field (name ".CREATOR") "MM")
        (field (name ".CHECKED PCB") "RF")
        (field (name ".CHECKED SCH") "RF")
      )
      (libsource (lib "Integrated_Library_FEDEVEL_APR_2015") (part "RC0805FR-07560RL"))
    )
    (comp (ref "R16")
      (value "1M")
      (footprint "R0805")
      (description "RES SMD 1M OHM 1% 1/8W 0805")
      (fields
        (field (name "MANUFACTURER") "Yageo")
        (field (name "MANUFACTURER PART NUMBER") "RC0805FR-071ML")
        (field (name ".CREATOR") "MM")
        (field (name ".CHECKED PCB") "RF")
        (field (name ".CHECKED SCH") "RF")
      )
      (libsource (lib "Integrated_Library_FEDEVEL_APR_2015") (part "RC0805FR-071ML"))
    )
    (comp (ref "R17")
      (value "560R")
      (footprint "R0805")
      (description "RES SMD 560 OHM 1% 1/8W 0805")
      (fields
        (field (name "MANUFACTURER") "Yageo")
        (field (name "MANUFACTURER PART NUMBER") "RC0805FR-07560RL")
        (field (name ".CREATOR") "MM")
        (field (name ".CHECKED PCB") "RF")
        (field (name ".CHECKED SCH") "RF")
      )
      (libsource (lib "Integrated_Library_FEDEVEL_APR_2015") (part "RC0805FR-07560RL"))
    )
    (comp (ref "R18")
      (value "10k")
      (footprint "R0805")
      (description "RES SMD 10K OHM 1% 1/8W 0805")
      (fields
        (field (name "MANUFACTURER") "Yageo")
        (field (name "MANUFACTURER PART NUMBER") "RC0805FR-0710KL")
        (field (name ".CREATOR") "MM")
        (field (name ".CHECKED PCB") "RF")
        (field (name ".CHECKED SCH") "RF")
      )
      (libsource (lib "Integrated_Library_FEDEVEL_APR_2015") (part "RC0805FR-0710KL"))
    )
    (comp (ref "R19")
      (value "10k")
      (footprint "R0805")
      (description "RES SMD 10K OHM 1% 1/8W 0805")
      (fields
        (field (name "MANUFACTURER") "Yageo")
        (field (name "MANUFACTURER PART NUMBER") "RC0805FR-0710KL")
        (field (name ".CREATOR") "MM")
        (field (name ".CHECKED PCB") "RF")
        (field (name ".CHECKED SCH") "RF")
      )
      (libsource (lib "Integrated_Library_FEDEVEL_APR_2015") (part "RC0805FR-0710KL"))
    )
    (comp (ref "R20")
      (value "10k")
      (footprint "R0805")
      (description "RES SMD 10K OHM 1% 1/8W 0805")
      (fields
        (field (name "MANUFACTURER") "Yageo")
        (field (name "MANUFACTURER PART NUMBER") "RC0805FR-0710KL")
        (field (name ".CREATOR") "MM")
        (field (name ".CHECKED PCB") "RF")
        (field (name ".CHECKED SCH") "RF")
      )
      (libsource (lib "Integrated_Library_FEDEVEL_APR_2015") (part "RC0805FR-0710KL"))
    )
    (comp (ref "R21")
      (value "10k")
      (footprint "R0805")
      (description "RES SMD 10K OHM 1% 1/8W 0805")
      (fields
        (field (name "MANUFACTURER") "Yageo")
        (field (name "MANUFACTURER PART NUMBER") "RC0805FR-0710KL")
        (field (name ".CREATOR") "MM")
        (field (name ".CHECKED PCB") "RF")
        (field (name ".CHECKED SCH") "RF")
      )
      (libsource (lib "Integrated_Library_FEDEVEL_APR_2015") (part "RC0805FR-0710KL"))
    )
    (comp (ref "R22")
      (value "560R")
      (footprint "R0805")
      (description "RES SMD 560 OHM 1% 1/8W 0805")
      (fields
        (field (name "MANUFACTURER") "Yageo")
        (field (name "MANUFACTURER PART NUMBER") "RC0805FR-07560RL")
        (field (name ".CREATOR") "MM")
        (field (name ".CHECKED PCB") "RF")
        (field (name ".CHECKED SCH") "RF")
      )
      (libsource (lib "Integrated_Library_FEDEVEL_APR_2015") (part "RC0805FR-07560RL"))
    )
    (comp (ref "R23")
      (value "22R")
      (footprint "R0805")
      (description "RES SMD 22 OHM 1% 1/8W 0805")
      (fields
        (field (name "MANUFACTURER") "Yageo")
        (field (name "MANUFACTURER PART NUMBER") "RC0805FR-0722RL")
        (field (name ".CREATOR") "MM")
        (field (name ".CHECKED PCB") "RF")
        (field (name ".CHECKED SCH") "RF")
      )
      (libsource (lib "Integrated_Library_FEDEVEL_APR_2015") (part "RC0805FR-0722RL"))
    )
    (comp (ref "R24")
      (value "22R")
      (footprint "R0805")
      (description "RES SMD 22 OHM 1% 1/8W 0805")
      (fields
        (field (name "MANUFACTURER") "Yageo")
        (field (name "MANUFACTURER PART NUMBER") "RC0805FR-0722RL")
        (field (name ".CREATOR") "MM")
        (field (name ".CHECKED PCB") "RF")
        (field (name ".CHECKED SCH") "RF")
      )
      (libsource (lib "Integrated_Library_FEDEVEL_APR_2015") (part "RC0805FR-0722RL"))
    )
    (comp (ref "R25")
      (value "22R")
      (footprint "R0805")
      (description "RES SMD 22 OHM 1% 1/8W 0805")
      (fields
        (field (name "MANUFACTURER") "Yageo")
        (field (name "MANUFACTURER PART NUMBER") "RC0805FR-0722RL")
        (field (name ".CREATOR") "MM")
        (field (name ".CHECKED PCB") "RF")
        (field (name ".CHECKED SCH") "RF")
      )
      (libsource (lib "Integrated_Library_FEDEVEL_APR_2015") (part "RC0805FR-0722RL"))
    )
    (comp (ref "R26")
      (value "0R")
      (footprint "R0805")
      (description "RES 0.0 OHM 1/8W 0805 SMD")
      (fields
        (field (name "MANUFACTURER") "Yageo")
        (field (name "MANUFACTURER PART NUMBER") "RC0805JR-070RL")
        (field (name ".CHECKED PCB") "RF")
        (field (name ".CHECKED SCH") "RF")
      )
      (libsource (lib "Integrated_Library_FEDEVEL_APR_2015") (part "RC0805JR-070RL"))
    )
    (comp (ref "R27")
      (value "0R")
      (footprint "R0805")
      (description "RES 0.0 OHM 1/8W 0805 SMD")
      (fields
        (field (name "MANUFACTURER") "Yageo")
        (field (name "MANUFACTURER PART NUMBER") "RC0805JR-070RL")
        (field (name ".CHECKED PCB") "RF")
        (field (name ".CHECKED SCH") "RF")
      )
      (libsource (lib "Integrated_Library_FEDEVEL_APR_2015") (part "RC0805JR-070RL"))
    )
    (comp (ref "R28")
      (value "0R")
      (footprint "R0805")
      (description "RES 0.0 OHM 1/8W 0805 SMD")
      (fields
        (field (name "MANUFACTURER") "Yageo")
        (field (name "MANUFACTURER PART NUMBER") "RC0805JR-070RL")
        (field (name ".CHECKED PCB") "RF")
        (field (name ".CHECKED SCH") "RF")
      )
      (libsource (lib "Integrated_Library_FEDEVEL_APR_2015") (part "RC0805JR-070RL"))
    )
    (comp (ref "SCKT FOR U1")
      (value "28-DIP Socket")
      (footprint "28_DIP_7.62mm_SOCKET")
      (description "CONN IC DIP SOCKET 28POS TIN")
      (fields
        (field (name "MANUFACTURER") "3M")
        (field (name "MANUFACTURER PART NUMBER") "4828-3004-CP")
        (field (name ".CREATOR") "MM")
        (field (name ".CHECKED PCB") "RF")
        (field (name ".CHECKED SCH") "RF")
      )
      (libsource (lib "Integrated_Library_FEDEVEL_APR_2015") (part "4828-3004-CP"))
    )
    (comp (ref "SW1")
      (value "1825910-6")
      (footprint "1825910-6")
      (description "SWITCH TACTILE SPST-NO 0.05A 24V")
      (fields
        (field (name "MANUFACTURER") "TE Connectivity")
        (field (name ".CREATOR") "MM")
        (field (name ".CHECKED PCB") "RF")
        (field (name ".CHECKED SCH") "RF")
      )
      (libsource (lib "Integrated_Library_FEDEVEL_APR_2015") (part "1825910-6"))
    )
    (comp (ref "SW2")
      (value "1825910-6")
      (footprint "1825910-6")
      (description "SWITCH TACTILE SPST-NO 0.05A 24V")
      (fields
        (field (name "MANUFACTURER") "TE Connectivity")
        (field (name ".CREATOR") "MM")
        (field (name ".CHECKED PCB") "RF")
        (field (name ".CHECKED SCH") "RF")
      )
      (libsource (lib "Integrated_Library_FEDEVEL_APR_2015") (part "1825910-6"))
    )
    (comp (ref "U1")
      (value "ATMEGA328P-PU")
      (footprint "28_DIP_7.62mm")
      (description "IC MCU 8BIT 32KB FLASH 28DIP")
      (fields
        (field (name "MANUFACTURER") "Atmel")
        (field (name ".CREATOR") "MM")
        (field (name ".CHECKED PCB") "RF")
        (field (name ".CHECKED SCH") "RF")
      )
      (libsource (lib "Integrated_Library_FEDEVEL_APR_2015") (part "ATMEGA328P-PU"))
    )
    (comp (ref "U2")
      (value "ATMEGA16U2-AU")
      (footprint "TQFP32")
      (description "IC MCU 8BIT 16KB FLASH 32TQFP")
      (fields
        (field (name "MANUFACTURER") "Atmel")
        (field (name ".CREATOR") "MM")
        (field (name ".CHECKED PCB") "RF")
        (field (name ".CHECKED SCH") "RF")
      )
      (libsource (lib "Integrated_Library_FEDEVEL_APR_2015") (part "ATMEGA16U2-AU"))
    )
    (comp (ref "U3")
      (value "TL1963A-33DCQR")
      (footprint "DCQ (R-PDSO-G6)")
      (description "IC REG LDO 3.3V 1.5A SOT223-6")
      (fields
        (field (name "MANUFACTURER") "Texas Instruments")
        (field (name ".CREATOR") "MM")
        (field (name ".CHECKED PCB") "RF")
        (field (name ".CHECKED SCH") "RF")
      )
      (libsource (lib "Integrated_Library_FEDEVEL_APR_2015") (part "TL1963A-33DCQR"))
    )
    (comp (ref "U4")
      (value "SN74AHC1G09DBVR")
      (footprint "DBV_SOT_23_5")
      (description "IC GATE AND SGL 2INP SOT23-5")
      (fields (field (name "MANUFACTURER") "Texas Instruments") (field (name ".CREATOR") "MM"))
      (libsource (lib "Integrated_Library_FEDEVEL_APR_2015") (part "SN74AHC1G09DBVR"))
    )
    (comp (ref "U5")
      (value "SN74AHC1G09DBVR")
      (footprint "DBV_SOT_23_5")
      (description "IC GATE AND SGL 2INP SOT23-5")
      (fields (field (name "MANUFACTURER") "Texas Instruments") (field (name ".CREATOR") "MM"))
      (libsource (lib "Integrated_Library_FEDEVEL_APR_2015") (part "SN74AHC1G09DBVR"))
    )
    (comp (ref "U6")
      (value "SN74AHC1G09DBVR")
      (footprint "DBV_SOT_23_5")
      (description "IC GATE AND SGL 2INP SOT23-5")
      (fields (field (name "MANUFACTURER") "Texas Instruments") (field (name ".CREATOR") "MM"))
      (libsource (lib "Integrated_Library_FEDEVEL_APR_2015") (part "SN74AHC1G09DBVR"))
    )
    (comp (ref "U7")
      (value "SN74AHC1G09DBVR")
      (footprint "DBV_SOT_23_5")
      (description "IC GATE AND SGL 2INP SOT23-5")
      (fields (field (name "MANUFACTURER") "Texas Instruments") (field (name ".CREATOR") "MM"))
      (libsource (lib "Integrated_Library_FEDEVEL_APR_2015") (part "SN74AHC1G09DBVR"))
    )
    (comp (ref "Y1")
      (value "ABM7-16.000MHZ-D2Y-T")
      (footprint "ABM7_v1_1_BIG")
      (description "CRYSTAL 16MHZ 18PF SMD")
      (fields
        (field (name "MANUFACTURER") "Abracon LLC")
        (field (name ".CREATOR") "MM")
        (field (name ".CHECKED PCB") "RF")
        (field (name ".CHECKED SCH") "RF")
      )
      (libsource (lib "Integrated_Library_FEDEVEL_APR_2015") (part "ABM7-16.000MHZ-D2Y-T"))
    )
    (comp (ref "Y2")
      (value "ABM7-16.000MHZ-D2Y-T")
      (footprint "ABM7_v1_1_BIG")
      (description "CRYSTAL 16MHZ 18PF SMD")
      (fields
        (field (name "MANUFACTURER") "Abracon LLC")
        (field (name ".CREATOR") "MM")
        (field (name ".CHECKED PCB") "RF")
        (field (name ".CHECKED SCH") "RF")
      )
      (libsource (lib "Integrated_Library_FEDEVEL_APR_2015") (part "ABM7-16.000MHZ-D2Y-T"))
    )
    (comp (ref "Z1")
      (value "CG0603MLC-05E")
      (footprint "R0603")
      (description "VARISTOR 0603")
      (fields
        (field (name "MANUFACTURER") "Bourns Inc.")
        (field (name ".CREATOR") "MM")
        (field (name ".CHECKED PCB") "RF")
        (field (name ".CHECKED SCH") "RF")
      )
      (libsource (lib "Integrated_Library_FEDEVEL_APR_2015") (part "CG0603MLC-05E"))
    )
    (comp (ref "Z2")
      (value "CG0603MLC-05E")
      (footprint "R0603")
      (description "VARISTOR 0603")
      (fields
        (field (name "MANUFACTURER") "Bourns Inc.")
        (field (name ".CREATOR") "MM")
        (field (name ".CHECKED PCB") "RF")
        (field (name ".CHECKED SCH") "RF")
      )
      (libsource (lib "Integrated_Library_FEDEVEL_APR_2015") (part "CG0603MLC-05E"))
    )
  )
  (nets
    (net (code "1") (name "+3V3") (class "Default")
      (node (ref "C13") (pin "1") (pinfunction "1_1") (pintype "passive"))
      (node (ref "C16") (pin "1") (pinfunction "1_1") (pintype "passive"))
      (node (ref "J1") (pin "4") (pinfunction "4_4") (pintype "passive"))
      (node (ref "JP4") (pin "3") (pinfunction "3_3") (pintype "passive"))
      (node (ref "R28") (pin "1") (pinfunction "1_1") (pintype "passive"))
      (node (ref "U3") (pin "4") (pinfunction "OUT_4") (pintype "passive"))
      (node (ref "U3") (pin "5") (pinfunction "SENSE_5") (pintype "passive"))
    )
    (net (code "2") (name "+5V") (class "Default")
      (node (ref "C12") (pin "1") (pinfunction "1_1") (pintype "passive"))
      (node (ref "C14") (pin "1") (pinfunction "1_1") (pintype "passive"))
      (node (ref "C2") (pin "1") (pinfunction "1_1") (pintype "passive"))
      (node (ref "C6") (pin "1") (pinfunction "1_1") (pintype "passive"))
      (node (ref "J1") (pin "5") (pinfunction "5_5") (pintype "passive"))
      (node (ref "J8") (pin "1") (pinfunction "1_1") (pintype "passive"))
      (node (ref "JP4") (pin "1") (pinfunction "1_1") (pintype "passive"))
      (node (ref "L1") (pin "2") (pinfunction "2_2") (pintype "passive"))
      (node (ref "R27") (pin "2") (pinfunction "2_2") (pintype "passive"))
      (node (ref "U2") (pin "31") (pinfunction "UVCC_31") (pintype "passive"))
      (node (ref "U3") (pin "1") (pinfunction "~{SHDN}_1") (pintype "passive"))
      (node (ref "U3") (pin "2") (pinfunction "IN_2") (pintype "passive"))
    )
    (net (code "3") (name "+5V{slash}3V3") (class "Default")
      (node (ref "C15") (pin "1") (pinfunction "1_1") (pintype "passive"))
      (node (ref "C17") (pin "1") (pinfunction "1_1") (pintype "passive"))
      (node (ref "C26") (pin "1") (pinfunction "1_1") (pintype "passive"))
      (node (ref "C28") (pin "1") (pinfunction "1_1") (pintype "passive"))
      (node (ref "C29") (pin "1") (pinfunction "1_1") (pintype "passive"))
      (node (ref "C30") (pin "1") (pinfunction "1_1") (pintype "passive"))
      (node (ref "C34") (pin "1") (pinfunction "1_1") (pintype "passive"))
      (node (ref "C8") (pin "1") (pinfunction "1_1") (pintype "passive"))
      (node (ref "D5") (pin "1") (pinfunction "Cathode_1") (pintype "passive"))
      (node (ref "D6") (pin "1") (pinfunction "Cathode_1") (pintype "passive"))
      (node (ref "FB1") (pin "1") (pinfunction "1_1") (pintype "passive"))
      (node (ref "FB2") (pin "1") (pinfunction "1_1") (pintype "passive"))
      (node (ref "FB3") (pin "1") (pinfunction "1_1") (pintype "passive"))
      (node (ref "J1") (pin "2") (pinfunction "2_2") (pintype "passive"))
      (node (ref "J5") (pin "2") (pinfunction "2_2") (pintype "passive"))
      (node (ref "J6") (pin "2") (pinfunction "2_2") (pintype "passive"))
      (node (ref "JP4") (pin "2") (pinfunction "2_2") (pintype "passive"))
      (node (ref "R1") (pin "2") (pinfunction "2_2") (pintype "passive"))
      (node (ref "R14") (pin "2") (pinfunction "2_2") (pintype "passive"))
      (node (ref "R15") (pin "2") (pinfunction "2_2") (pintype "passive"))
      (node (ref "R17") (pin "2") (pinfunction "2_2") (pintype "passive"))
      (node (ref "R18") (pin "2") (pinfunction "2_2") (pintype "passive"))
      (node (ref "R19") (pin "2") (pinfunction "2_2") (pintype "passive"))
      (node (ref "R2") (pin "2") (pinfunction "2_2") (pintype "passive"))
      (node (ref "R20") (pin "2") (pinfunction "2_2") (pintype "passive"))
      (node (ref "R21") (pin "2") (pinfunction "2_2") (pintype "passive"))
      (node (ref "R27") (pin "1") (pinfunction "1_1") (pintype "passive"))
      (node (ref "R28") (pin "2") (pinfunction "2_2") (pintype "passive"))
      (node (ref "R3") (pin "2") (pinfunction "2_2") (pintype "passive"))
      (node (ref "R4") (pin "2") (pinfunction "2_2") (pintype "passive"))
      (node (ref "U4") (pin "5") (pinfunction "VCC_5") (pintype "power_in"))
      (node (ref "U5") (pin "5") (pinfunction "VCC_5") (pintype "power_in"))
      (node (ref "U6") (pin "5") (pinfunction "VCC_5") (pintype "power_in"))
      (node (ref "U7") (pin "5") (pinfunction "VCC_5") (pintype "power_in"))
    )
    (net (code "4") (name "+AREF") (class "Default")
      (node (ref "C21") (pin "1") (pinfunction "1_1") (pintype "passive"))
      (node (ref "C24") (pin "1") (pinfunction "1_1") (pintype "passive"))
      (node (ref "J4") (pin "8") (pinfunction "8_8") (pintype "passive"))
      (node (ref "U1") (pin "21") (pinfunction "AREF_21") (pintype "passive"))
    )
    (net (code "5") (name "/+3V3_16U2_UCAP") (class "Default")
      (node (ref "C7") (pin "2") (pinfunction "2_2") (pintype "passive"))
      (node (ref "R26") (pin "1") (pinfunction "1_1") (pintype "passive"))
      (node (ref "U2") (pin "27") (pinfunction "UCAP_27") (pintype "passive"))
    )
    (net (code "6") (name "/+5V_USB") (class "Default")
      (node (ref "C1") (pin "1") (pinfunction "1_1") (pintype "passive"))
      (node (ref "J7") (pin "1") (pinfunction "P1_1") (pintype "passive"))
      (node (ref "L1") (pin "1") (pinfunction "1_1") (pintype "passive"))
    )
    (net (code "7") (name "/+5V{slash}3V3_16U2") (class "Default")
      (node (ref "C3") (pin "1") (pinfunction "1_1") (pintype "passive"))
      (node (ref "C4") (pin "1") (pinfunction "1_1") (pintype "passive"))
      (node (ref "C5") (pin "1") (pinfunction "1_1") (pintype "passive"))
      (node (ref "FB1") (pin "2") (pinfunction "2_2") (pintype "passive"))
      (node (ref "R26") (pin "2") (pinfunction "2_2") (pintype "passive"))
      (node (ref "U2") (pin "32") (pinfunction "AVCC_32") (pintype "passive"))
      (node (ref "U2") (pin "4") (pinfunction "VCC_4") (pintype "passive"))
    )
    (net (code "8") (name "/+5V{slash}3V3_328P_AVCC") (class "Default")
      (node (ref "C22") (pin "1") (pinfunction "1_1") (pintype "passive"))
      (node (ref "C23") (pin "1") (pinfunction "1_1") (pintype "passive"))
      (node (ref "FB3") (pin "2") (pinfunction "2_2") (pintype "passive"))
      (node (ref "U1") (pin "20") (pinfunction "AVCC_20") (pintype "passive"))
    )
    (net (code "9") (name "/+5V{slash}3V3_328P_VCC") (class "Default")
      (node (ref "C19") (pin "1") (pinfunction "1_1") (pintype "passive"))
      (node (ref "C20") (pin "1") (pinfunction "1_1") (pintype "passive"))
      (node (ref "FB2") (pin "2") (pinfunction "2_2") (pintype "passive"))
      (node (ref "U1") (pin "7") (pinfunction "VCC_7") (pintype "passive"))
    )
    (net (code "10") (name "/16U2PROG_328P_RESETn") (class "Default")
      (node (ref "JP1") (pin "2") (pinfunction "2_2") (pintype "passive"))
      (node (ref "R1") (pin "1") (pinfunction "1_1") (pintype "passive"))
      (node (ref "U2") (pin "13") (pinfunction "~{CTS}_/~{_HWB}_/_T0_/_AIN6_/_INT7_/_PD7_13") (pintype "passive"))
    )
    (net (code "11") (name "/16U2_16MHZ_XTAL1") (class "Default")
      (node (ref "C10") (pin "2") (pinfunction "2_2") (pintype "passive"))
      (node (ref "R9") (pin "1") (pinfunction "1_1") (pintype "passive"))
      (node (ref "U2") (pin "1") (pinfunction "XTAL1_1") (pintype "passive"))
      (node (ref "Y2") (pin "1") (pinfunction "1_1") (pintype "passive"))
    )
    (net (code "12") (name "/16U2_16MHZ_XTAL2") (class "Default")
      (node (ref "C9") (pin "2") (pinfunction "2_2") (pintype "passive"))
      (node (ref "R9") (pin "2") (pinfunction "2_2") (pintype "passive"))
      (node (ref "U2") (pin "2") (pinfunction "XTAL2_/_PC0_2") (pintype "passive"))
      (node (ref "Y2") (pin "2") (pinfunction "2_2") (pintype "passive"))
    )
    (net (code "13") (name "/16U2_BUF_RESETn") (class "Default")
      (node (ref "C31") (pin "1") (pinfunction "1_1") (pintype "passive"))
      (node (ref "R23") (pin "2") (pinfunction "2_2") (pintype "passive"))
      (node (ref "U5") (pin "1") (pinfunction "A_1") (pintype "passive"))
      (node (ref "U5") (pin "2") (pinfunction "B_2") (pintype "passive"))
    )
    (net (code "14") (name "/16U2_HDR_RESETn") (class "Default")
      (node (ref "J6") (pin "5") (pinfunction "5_5") (pintype "passive"))
      (node (ref "JP3") (pin "3") (pinfunction "3_3") (pintype "passive"))
    )
    (net (code "15") (name "/16U2_MISO") (class "Default")
      (node (ref "J6") (pin "1") (pinfunction "1_1") (pintype "passive"))
      (node (ref "U2") (pin "17") (pinfunction "PDO_/_MISO_/_PCINT3_/_PB3_17") (pintype "passive"))
    )
    (net (code "16") (name "/16U2_MOSI") (class "Default")
      (node (ref "J6") (pin "4") (pinfunction "4_4") (pintype "passive"))
      (node (ref "U2") (pin "16") (pinfunction "PDI_/_MOSI_/_PCINT2_/_PB2_16") (pintype "passive"))
    )
    (net (code "17") (name "/16U2_PB4") (class "Default")
      (node (ref "JP2") (pin "1") (pinfunction "1_1") (pintype "passive"))
      (node (ref "JP3") (pin "2") (pinfunction "2_2") (pintype "passive"))
      (node (ref "U2") (pin "18") (pinfunction "T1_/_PCINT4_/_PB4_18") (pintype "passive"))
    )
    (net (code "18") (name "/16U2_PB5") (class "Default")
      (node (ref "JP2") (pin "3") (pinfunction "3_3") (pintype "passive"))
      (node (ref "U2") (pin "19") (pinfunction "PCINT5_/_PB5_19") (pintype "passive"))
    )
    (net (code "19") (name "/16U2_PB6") (class "Default")
      (node (ref "JP2") (pin "2") (pinfunction "2_2") (pintype "passive"))
      (node (ref "U2") (pin "20") (pinfunction "PCINT6_/_PB6_20") (pintype "passive"))
    )
    (net (code "20") (name "/16U2_PB7") (class "Default")
      (node (ref "JP2") (pin "4") (pinfunction "4_4") (pintype "passive"))
      (node (ref "U2") (pin "21") (pinfunction "OC.0A_/_OC.1C_/_PCINT7_/_PB7_21") (pintype "passive"))
    )
    (net (code "21") (name "/16U2_RESETn") (class "Default")
      (node (ref "JP3") (pin "4") (pinfunction "4_4") (pintype "passive"))
      (node (ref "R4") (pin "1") (pinfunction "1_1") (pintype "passive"))
      (node (ref "U2") (pin "24") (pinfunction "PC1_/~{_RESET}_/_DW_24") (pintype "passive"))
      (node (ref "U5") (pin "4") (pinfunction "Y_4") (pintype "passive"))
    )
    (net (code "22") (name "/16U2_RXD") (class "Default")
      (node (ref "R11") (pin "1") (pinfunction "1_1") (pintype "passive"))
      (node (ref "U2") (pin "8") (pinfunction "RXD1_/_AIN1_/_INT2_/_PD2_8") (pintype "passive"))
    )
    (net (code "23") (name "/16U2_RX_LED") (class "Default")
      (node (ref "D4") (pin "1") (pinfunction "cathode_1") (pintype "passive"))
      (node (ref "U2") (pin "10") (pinfunction "AIN3_/_INT5_/_PD4_10") (pintype "passive"))
    )
    (net (code "24") (name "/16U2_SCLK") (class "Default")
      (node (ref "J6") (pin "3") (pinfunction "3_3") (pintype "passive"))
      (node (ref "R5") (pin "2") (pinfunction "2_2") (pintype "passive"))
    )
    (net (code "25") (name "/16U2_SCLK_R") (class "Default")
      (node (ref "R5") (pin "1") (pinfunction "1_1") (pintype "passive"))
      (node (ref "U2") (pin "15") (pinfunction "SCLK_/_PCINT1_/_PB1_15") (pintype "passive"))
    )
    (net (code "26") (name "/16U2_TXD") (class "Default")
      (node (ref "R10") (pin "1") (pinfunction "1_1") (pintype "passive"))
      (node (ref "U2") (pin "9") (pinfunction "TXD1_/_INT3_/_PD3_9") (pintype "passive"))
    )
    (net (code "27") (name "/16U2_TX_LED") (class "Default")
      (node (ref "D3") (pin "1") (pinfunction "cathode_1") (pintype "passive"))
      (node (ref "U2") (pin "11") (pinfunction "XCK_/_AIN4_/_PCINT12_/_PD5_11") (pintype "passive"))
    )
    (net (code "28") (name "/328P_16MHZ_XTAL1") (class "Default")
      (node (ref "C27") (pin "2") (pinfunction "2_2") (pintype "passive"))
      (node (ref "R16") (pin "1") (pinfunction "1_1") (pintype "passive"))
      (node (ref "U1") (pin "9") (pinfunction "PB6_/_PCINT6_/_TOSC1_/_XTAL1_9") (pintype "passive"))
      (node (ref "Y1") (pin "1") (pinfunction "1_1") (pintype "passive"))
    )
    (net (code "29") (name "/328P_16MHZ_XTAL2") (class "Default")
      (node (ref "C25") (pin "2") (pinfunction "2_2") (pintype "passive"))
      (node (ref "R16") (pin "2") (pinfunction "2_2") (pintype "passive"))
      (node (ref "U1") (pin "10") (pinfunction "PB7_/_PCINT7_/_TOSC2_/_XTAL2_10") (pintype "passive"))
      (node (ref "Y1") (pin "2") (pinfunction "2_2") (pintype "passive"))
    )
    (net (code "30") (name "/328P_AUTORESETn") (class "Default")
      (node (ref "C11") (pin "1") (pinfunction "1_1") (pintype "passive"))
      (node (ref "R18") (pin "1") (pinfunction "1_1") (pintype "passive"))
      (node (ref "U6") (pin "1") (pinfunction "A_1") (pintype "passive"))
    )
    (net (code "31") (name "/328P_BUF_RESETn") (class "Default")
      (node (ref "C32") (pin "1") (pinfunction "1_1") (pintype "passive"))
      (node (ref "R24") (pin "2") (pinfunction "2_2") (pintype "passive"))
      (node (ref "U6") (pin "2") (pinfunction "B_2") (pintype "passive"))
    )
    (net (code "32") (name "/328P_RESETn") (class "Default")
      (node (ref "J1") (pin "3") (pinfunction "3_3") (pintype "passive"))
      (node (ref "J5") (pin "5") (pinfunction "5_5") (pintype "passive"))
      (node (ref "JP3") (pin "1") (pinfunction "1_1") (pintype "passive"))
      (node (ref "R14") (pin "1") (pinfunction "1_1") (pintype "passive"))
      (node (ref "U1") (pin "1") (pinfunction "PC6_/_PCINT14_/~{_RESET}_1") (pintype "passive"))
      (node (ref "U6") (pin "4") (pinfunction "Y_4") (pintype "passive"))
    )
    (net (code "33") (name "/AD0") (class "Default")
      (node (ref "J2") (pin "1") (pinfunction "1_1") (pintype "passive"))
      (node (ref "U1") (pin "23") (pinfunction "PCINT8_/_ADC0_/_PC0_23") (pintype "passive"))
    )
    (net (code "34") (name "/AD1") (class "Default")
      (node (ref "J2") (pin "2") (pinfunction "2_2") (pintype "passive"))
      (node (ref "U1") (pin "24") (pinfunction "PCINT9_/_ADC1_/_PC1_24") (pintype "passive"))
    )
    (net (code "35") (name "/AD2") (class "Default")
      (node (ref "J2") (pin "3") (pinfunction "3_3") (pintype "passive"))
      (node (ref "U1") (pin "25") (pinfunction "PCINT10_/_ADC2_/_PC2_25") (pintype "passive"))
    )
    (net (code "36") (name "/AD3") (class "Default")
      (node (ref "J2") (pin "4") (pinfunction "4_4") (pintype "passive"))
      (node (ref "U1") (pin "26") (pinfunction "PCINT11_/_ADC3_/_PC3_26") (pintype "passive"))
    )
    (net (code "37") (name "/AD4{slash}SDA") (class "Default")
      (node (ref "J2") (pin "5") (pinfunction "5_5") (pintype "passive"))
      (node (ref "J4") (pin "9") (pinfunction "9_9") (pintype "passive"))
      (node (ref "U1") (pin "27") (pinfunction "SDA_/_PCINT12_/_ADC4_/_PC4_27") (pintype "passive"))
    )
    (net (code "38") (name "/AD5{slash}SCL") (class "Default")
      (node (ref "J2") (pin "6") (pinfunction "6_6") (pintype "passive"))
      (node (ref "J4") (pin "10") (pinfunction "10_10") (pintype "passive"))
      (node (ref "U1") (pin "28") (pinfunction "SCL_/_PCINT13_/_ADC5_/_PC5_28") (pintype "passive"))
    )
    (net (code "39") (name "/BUTTON_RESETn") (class "Default")
      (node (ref "D6") (pin "2") (pinfunction "Anode_2") (pintype "passive"))
      (node (ref "R20") (pin "1") (pinfunction "1_1") (pintype "passive"))
      (node (ref "R24") (pin "1") (pinfunction "1_1") (pintype "passive"))
      (node (ref "SW1") (pin "1") (pinfunction "1_1") (pintype "passive"))
      (node (ref "SW1") (pin "2") (pinfunction "2_2") (pintype "passive"))
    )
    (net (code "40") (name "/CON_USB_N") (class "Default")
      (node (ref "J7") (pin "2") (pinfunction "P2_2") (pintype "passive"))
      (node (ref "R6") (pin "1") (pinfunction "1_1") (pintype "passive"))
      (node (ref "Z1") (pin "2") (pinfunction "2_2") (pintype "passive"))
    )
    (net (code "41") (name "/CON_USB_P") (class "Default")
      (node (ref "J7") (pin "3") (pinfunction "P3_3") (pintype "passive"))
      (node (ref "R7") (pin "1") (pinfunction "1_1") (pintype "passive"))
      (node (ref "Z2") (pin "2") (pinfunction "2_2") (pintype "passive"))
    )
    (net (code "42") (name "/IO0") (class "Default")
      (node (ref "J3") (pin "1") (pinfunction "1_1") (pintype "passive"))
      (node (ref "R10") (pin "2") (pinfunction "2_2") (pintype "passive"))
      (node (ref "U1") (pin "2") (pinfunction "RXD_/_PCINT16_/_PD0_2") (pintype "passive"))
    )
    (net (code "43") (name "/IO1") (class "Default")
      (node (ref "J3") (pin "2") (pinfunction "2_2") (pintype "passive"))
      (node (ref "R11") (pin "2") (pinfunction "2_2") (pintype "passive"))
      (node (ref "U1") (pin "3") (pinfunction "TXD_/_PCINT17_/_PD1_3") (pintype "passive"))
    )
    (net (code "44") (name "/IO2") (class "Default")
      (node (ref "J3") (pin "3") (pinfunction "3_3") (pintype "passive"))
      (node (ref "U1") (pin "4") (pinfunction "INT0_/_PCINT18_/_PD2_4") (pintype "passive"))
    )
    (net (code "45") (name "/IO3") (class "Default")
      (node (ref "J3") (pin "4") (pinfunction "4_4") (pintype "passive"))
      (node (ref "U1") (pin "5") (pinfunction "OC2B_/_INT1_/_PCINT19_/_PD3_5") (pintype "passive"))
    )
    (net (code "46") (name "/IO4") (class "Default")
      (node (ref "J3") (pin "5") (pinfunction "5_5") (pintype "passive"))
      (node (ref "U1") (pin "6") (pinfunction "XCK_/_T0_/_PCINT20_/_PD4_6") (pintype "passive"))
    )
    (net (code "47") (name "/IO5") (class "Default")
      (node (ref "J3") (pin "6") (pinfunction "6_6") (pintype "passive"))
      (node (ref "U1") (pin "11") (pinfunction "OC0B_/_T1_/_PCINT21_/_PD5_11") (pintype "passive"))
    )
    (net (code "48") (name "/IO6") (class "Default")
      (node (ref "J3") (pin "7") (pinfunction "7_7") (pintype "passive"))
      (node (ref "U1") (pin "12") (pinfunction "OC0A_/_AIN0_/_PCINT22_/_PD6_12") (pintype "passive"))
    )
    (net (code "49") (name "/IO7") (class "Default")
      (node (ref "J3") (pin "8") (pinfunction "8_8") (pintype "passive"))
      (node (ref "U1") (pin "13") (pinfunction "AIN1_/_PCINT23_/_PD7_13") (pintype "passive"))
    )
    (net (code "50") (name "/IO8") (class "Default")
      (node (ref "J4") (pin "1") (pinfunction "1_1") (pintype "passive"))
      (node (ref "R22") (pin "1") (pinfunction "1_1") (pintype "passive"))
      (node (ref "U1") (pin "14") (pinfunction "CLKO_/_ICP1_/_PCINT0_/_PB0_14") (pintype "passive"))
    )
    (net (code "51") (name "/IO9") (class "Default")
      (node (ref "J4") (pin "2") (pinfunction "2_2") (pintype "passive"))
      (node (ref "U1") (pin "15") (pinfunction "OC1A_/_PCINT1_/_PB1_15") (pintype "passive"))
    )
    (net (code "52") (name "/MISO") (class "Default")
      (node (ref "J4") (pin "5") (pinfunction "5_5") (pintype "passive"))
      (node (ref "J5") (pin "1") (pinfunction "1_1") (pintype "passive"))
      (node (ref "U1") (pin "18") (pinfunction "MISO_/_PCINT4_/_PB4_18") (pintype "passive"))
    )
    (net (code "53") (name "/MOSI") (class "Default")
      (node (ref "J4") (pin "4") (pinfunction "4_4") (pintype "passive"))
      (node (ref "J5") (pin "4") (pinfunction "4_4") (pintype "passive"))
      (node (ref "U1") (pin "17") (pinfunction "MOSI_/_OC2A_/_PCINT3_/_PB3_17") (pintype "passive"))
    )
    (net (code "54") (name "/SCK") (class "Default")
      (node (ref "J4") (pin "6") (pinfunction "6_6") (pintype "passive"))
      (node (ref "J5") (pin "3") (pinfunction "3_3") (pintype "passive"))
      (node (ref "R13") (pin "2") (pinfunction "2_2") (pintype "passive"))
      (node (ref "U4") (pin "1") (pinfunction "A_1") (pintype "passive"))
      (node (ref "U4") (pin "2") (pinfunction "B_2") (pintype "passive"))
    )
    (net (code "55") (name "/SCK_R") (class "Default")
      (node (ref "R13") (pin "1") (pinfunction "1_1") (pintype "passive"))
      (node (ref "U1") (pin "19") (pinfunction "SCK_/_PCINT5_/_PB5_19") (pintype "passive"))
    )
    (net (code "56") (name "/SS") (class "Default")
      (node (ref "J4") (pin "3") (pinfunction "3_3") (pintype "passive"))
      (node (ref "U1") (pin "16") (pinfunction "~{SS}_/_OC1B_/_PCINT2_/_PB2_16") (pintype "passive"))
    )
    (net (code "57") (name "/USB_N") (class "Default")
      (node (ref "R6") (pin "2") (pinfunction "2_2") (pintype "passive"))
      (node (ref "U2") (pin "30") (pinfunction "D-_30") (pintype "passive"))
    )
    (net (code "58") (name "/USB_P") (class "Default")
      (node (ref "R7") (pin "2") (pinfunction "2_2") (pintype "passive"))
      (node (ref "U2") (pin "29") (pinfunction "D+_29") (pintype "passive"))
    )
    (net (code "59") (name "/USER_BUTTON") (class "Default")
      (node (ref "R21") (pin "1") (pinfunction "1_1") (pintype "passive"))
      (node (ref "R25") (pin "1") (pinfunction "1_1") (pintype "passive"))
      (node (ref "SW2") (pin "1") (pinfunction "1_1") (pintype "passive"))
      (node (ref "SW2") (pin "2") (pinfunction "2_2") (pintype "passive"))
    )
    (net (code "60") (name "/USER_BUTTON_BUF") (class "Default")
      (node (ref "C33") (pin "1") (pinfunction "1_1") (pintype "passive"))
      (node (ref "R25") (pin "2") (pinfunction "2_2") (pintype "passive"))
      (node (ref "U7") (pin "1") (pinfunction "A_1") (pintype "passive"))
      (node (ref "U7") (pin "2") (pinfunction "B_2") (pintype "passive"))
    )
    (net (code "61") (name "GND") (class "Default")
      (node (ref "C1") (pin "2") (pinfunction "2_2") (pintype "passive"))
      (node (ref "C10") (pin "1") (pinfunction "1_1") (pintype "passive"))
      (node (ref "C12") (pin "2") (pinfunction "2_2") (pintype "passive"))
      (node (ref "C13") (pin "2") (pinfunction "2_2") (pintype "passive"))
      (node (ref "C14") (pin "2") (pinfunction "2_2") (pintype "passive"))
      (node (ref "C15") (pin "2") (pinfunction "2_2") (pintype "passive"))
      (node (ref "C16") (pin "2") (pinfunction "2_2") (pintype "passive"))
      (node (ref "C17") (pin "2") (pinfunction "2_2") (pintype "passive"))
      (node (ref "C19") (pin "2") (pinfunction "2_2") (pintype "passive"))
      (node (ref "C2") (pin "2") (pinfunction "2_2") (pintype "passive"))
      (node (ref "C20") (pin "2") (pinfunction "2_2") (pintype "passive"))
      (node (ref "C21") (pin "2") (pinfunction "2_2") (pintype "passive"))
      (node (ref "C22") (pin "2") (pinfunction "2_2") (pintype "passive"))
      (node (ref "C23") (pin "2") (pinfunction "2_2") (pintype "passive"))
      (node (ref "C24") (pin "2") (pinfunction "2_2") (pintype "passive"))
      (node (ref "C25") (pin "1") (pinfunction "1_1") (pintype "passive"))
      (node (ref "C26") (pin "2") (pinfunction "2_2") (pintype "passive"))
      (node (ref "C27") (pin "1") (pinfunction "1_1") (pintype "passive"))
      (node (ref "C28") (pin "2") (pinfunction "2_2") (pintype "passive"))
      (node (ref "C29") (pin "2") (pinfunction "2_2") (pintype "passive"))
      (node (ref "C3") (pin "2") (pinfunction "2_2") (pintype "passive"))
      (node (ref "C30") (pin "2") (pinfunction "2_2") (pintype "passive"))
      (node (ref "C31") (pin "2") (pinfunction "2_2") (pintype "passive"))
      (node (ref "C32") (pin "2") (pinfunction "2_2") (pintype "passive"))
      (node (ref "C33") (pin "2") (pinfunction "2_2") (pintype "passive"))
      (node (ref "C34") (pin "2") (pinfunction "2_2") (pintype "passive"))
      (node (ref "C4") (pin "2") (pinfunction "2_2") (pintype "passive"))
      (node (ref "C5") (pin "2") (pinfunction "2_2") (pintype "passive"))
      (node (ref "C6") (pin "2") (pinfunction "2_2") (pintype "passive"))
      (node (ref "C7") (pin "1") (pinfunction "1_1") (pintype "passive"))
      (node (ref "C8") (pin "2") (pinfunction "2_2") (pintype "passive"))
      (node (ref "C9") (pin "1") (pinfunction "1_1") (pintype "passive"))
      (node (ref "D1") (pin "1") (pinfunction "cathode_1") (pintype "passive"))
      (node (ref "J1") (pin "6") (pinfunction "6_6") (pintype "passive"))
      (node (ref "J1") (pin "7") (pinfunction "7_7") (pintype "passive"))
      (node (ref "J4") (pin "7") (pinfunction "7_7") (pintype "passive"))
      (node (ref "J5") (pin "6") (pinfunction "6_6") (pintype "passive"))
      (node (ref "J6") (pin "6") (pinfunction "6_6") (pintype "passive"))
      (node (ref "J7") (pin "10") (pinfunction "10_10") (pintype "passive"))
      (node (ref "J7") (pin "11") (pinfunction "11_11") (pintype "passive"))
      (node (ref "J7") (pin "5") (pinfunction "P5_5") (pintype "passive"))
      (node (ref "J7") (pin "6") (pinfunction "6_6") (pintype "passive"))
      (node (ref "J7") (pin "7") (pinfunction "7_7") (pintype "passive"))
      (node (ref "J7") (pin "8") (pinfunction "8_8") (pintype "passive"))
      (node (ref "J7") (pin "9") (pinfunction "9_9") (pintype "passive"))
      (node (ref "J9") (pin "1") (pinfunction "1_1") (pintype "passive"))
      (node (ref "MH1") (pin "1") (pinfunction "1_1") (pintype "passive"))
      (node (ref "MH2") (pin "1") (pinfunction "1_1") (pintype "passive"))
      (node (ref "MH3") (pin "1") (pinfunction "1_1") (pintype "passive"))
      (node (ref "R12") (pin "2") (pinfunction "2_2") (pintype "passive"))
      (node (ref "R8") (pin "2") (pinfunction "2_2") (pintype "passive"))
      (node (ref "SW1") (pin "3") (pinfunction "MECH1_3") (pintype "passive"))
      (node (ref "SW1") (pin "4") (pinfunction "MECH2_4") (pintype "passive"))
      (node (ref "SW2") (pin "3") (pinfunction "MECH1_3") (pintype "passive"))
      (node (ref "SW2") (pin "4") (pinfunction "MECH2_4") (pintype "passive"))
      (node (ref "U1") (pin "22") (pinfunction "GND_2_22") (pintype "passive"))
      (node (ref "U1") (pin "8") (pinfunction "GND_1_8") (pintype "passive"))
      (node (ref "U2") (pin "28") (pinfunction "UGND_28") (pintype "passive"))
      (node (ref "U2") (pin "3") (pinfunction "GND_3") (pintype "passive"))
      (node (ref "U3") (pin "3") (pinfunction "GND_3") (pintype "passive"))
      (node (ref "U3") (pin "6") (pinfunction "EPAD_6") (pintype "passive"))
      (node (ref "U4") (pin "3") (pinfunction "GND_3") (pintype "power_in"))
      (node (ref "U5") (pin "3") (pinfunction "GND_3") (pintype "power_in"))
      (node (ref "U6") (pin "3") (pinfunction "GND_3") (pintype "power_in"))
      (node (ref "U7") (pin "3") (pinfunction "GND_3") (pintype "power_in"))
      (node (ref "Z1") (pin "1") (pinfunction "1_1") (pintype "passive"))
      (node (ref "Z2") (pin "1") (pinfunction "1_1") (pintype "passive"))
    )
    (net (code "62") (name "Net-(C11-Pad2)") (class "Default")
      (node (ref "C11") (pin "2") (pinfunction "2_2") (pintype "passive"))
      (node (ref "JP1") (pin "1") (pinfunction "1_1") (pintype "passive"))
    )
    (net (code "63") (name "Net-(D1-ANODE)") (class "Default")
      (node (ref "D1") (pin "2") (pinfunction "ANODE_2") (pintype "passive"))
      (node (ref "R17") (pin "1") (pinfunction "1_1") (pintype "passive"))
    )
    (net (code "64") (name "Net-(D2-ANODE)") (class "Default")
      (node (ref "D2") (pin "2") (pinfunction "ANODE_2") (pintype "passive"))
      (node (ref "R15") (pin "1") (pinfunction "1_1") (pintype "passive"))
    )
    (net (code "65") (name "Net-(D2-cathode)") (class "Default")
      (node (ref "D2") (pin "1") (pinfunction "cathode_1") (pintype "passive"))
      (node (ref "U4") (pin "4") (pinfunction "Y_4") (pintype "passive"))
    )
    (net (code "66") (name "Net-(D3-ANODE)") (class "Default")
      (node (ref "D3") (pin "2") (pinfunction "ANODE_2") (pintype "passive"))
      (node (ref "R2") (pin "1") (pinfunction "1_1") (pintype "passive"))
    )
    (net (code "67") (name "Net-(D4-ANODE)") (class "Default")
      (node (ref "D4") (pin "2") (pinfunction "ANODE_2") (pintype "passive"))
      (node (ref "R3") (pin "1") (pinfunction "1_1") (pintype "passive"))
    )
    (net (code "68") (name "Net-(D5-Anode)") (class "Default")
      (node (ref "D5") (pin "2") (pinfunction "Anode_2") (pintype "passive"))
      (node (ref "R19") (pin "1") (pinfunction "1_1") (pintype "passive"))
      (node (ref "R23") (pin "1") (pinfunction "1_1") (pintype "passive"))
    )
    (net (code "69") (name "Net-(J7-P4)") (class "Default")
      (node (ref "J7") (pin "4") (pinfunction "P4_4") (pintype "passive"))
      (node (ref "R8") (pin "1") (pinfunction "1_1") (pintype "passive"))
    )
    (net (code "70") (name "Net-(JP1-Pad3)") (class "Default")
      (node (ref "JP1") (pin "3") (pinfunction "3_3") (pintype "passive"))
      (node (ref "R12") (pin "1") (pinfunction "1_1") (pintype "passive"))
    )
    (net (code "71") (name "Net-(U7-Y)") (class "Default")
      (node (ref "R22") (pin "2") (pinfunction "2_2") (pintype "passive"))
      (node (ref "U7") (pin "4") (pinfunction "Y_4") (pintype "passive"))
    )
    (net (code "72") (name "unconnected-(J1-Pad1)") (class "Default")
      (node (ref "J1") (pin "1") (pinfunction "1_1") (pintype "passive+no_connect"))
    )
    (net (code "73") (name "unconnected-(J1-Pad8)") (class "Default")
      (node (ref "J1") (pin "8") (pinfunction "8_8") (pintype "passive+no_connect"))
    )
    (net (code "74") (name "unconnected-(MH4-Pad1)") (class "Default")
      (node (ref "MH4") (pin "1") (pinfunction "1_1") (pintype "passive+no_connect"))
    )
    (net (code "75") (name "unconnected-(U2-AIN0_{slash}_INT1_{slash}_PD1-Pad7)") (class "Default")
      (node (ref "U2") (pin "7") (pinfunction "AIN0_/_INT1_/_PD1_7") (pintype "passive+no_connect"))
    )
    (net (code "76") (name "unconnected-(U2-AIN2_{slash}_PCINT11_{slash}_PC2-Pad5)") (class "Default")
      (node (ref "U2") (pin "5") (pinfunction "AIN2_/_PCINT11_/_PC2_5") (pintype "passive+no_connect"))
    )
    (net (code "77") (name "unconnected-(U2-CLKO_{slash}_ICP1_{slash}_INT4_{slash}_PC7-Pad22)") (class "Default")
      (node (ref "U2") (pin "22") (pinfunction "CLKO_/_ICP1_/_INT4_/_PC7_22") (pintype "passive+no_connect"))
    )
    (net (code "78") (name "unconnected-(U2-OC.0B_{slash}_INT0_{slash}_PD0-Pad6)") (class "Default")
      (node (ref "U2") (pin "6") (pinfunction "OC.0B_/_INT0_/_PD0_6") (pintype "passive+no_connect"))
    )
    (net (code "79") (name "unconnected-(U2-OC.1A_{slash}_PCINT8_{slash}_PC6-Pad23)") (class "Default")
      (node (ref "U2") (pin "23") (pinfunction "OC.1A_/_PCINT8_/_PC6_23") (pintype "passive+no_connect"))
    )
    (net (code "80") (name "unconnected-(U2-OC.1B_{slash}_PCINT9_{slash}_PC5-Pad25)") (class "Default")
      (node (ref "U2") (pin "25") (pinfunction "OC.1B_/_PCINT9_/_PC5_25") (pintype "passive+no_connect"))
    )
    (net (code "81") (name "unconnected-(U2-PCINT10_{slash}_PC4-Pad26)") (class "Default")
      (node (ref "U2") (pin "26") (pinfunction "PCINT10_/_PC4_26") (pintype "passive+no_connect"))
    )
    (net (code "82") (name "unconnected-(U2-~{RTS}_{slash}_AIN5_{slash}_INT6_{slash}_PD6-Pad12)") (class "Default")
      (node (ref "U2") (pin "12") (pinfunction "~{RTS}_/_AIN5_/_INT6_/_PD6_12") (pintype "passive"))
    )
    (net (code "83") (name "unconnected-(U2-~{SS}_{slash}_PCINT0_{slash}_PB0-Pad14)") (class "Default")
      (node (ref "U2") (pin "14") (pinfunction "~{SS}_/_PCINT0_/_PB0_14") (pintype "passive+no_connect"))
    )
  )
)
